# Clock.net
KiCad netlist of a schematic drawn in EAGLE
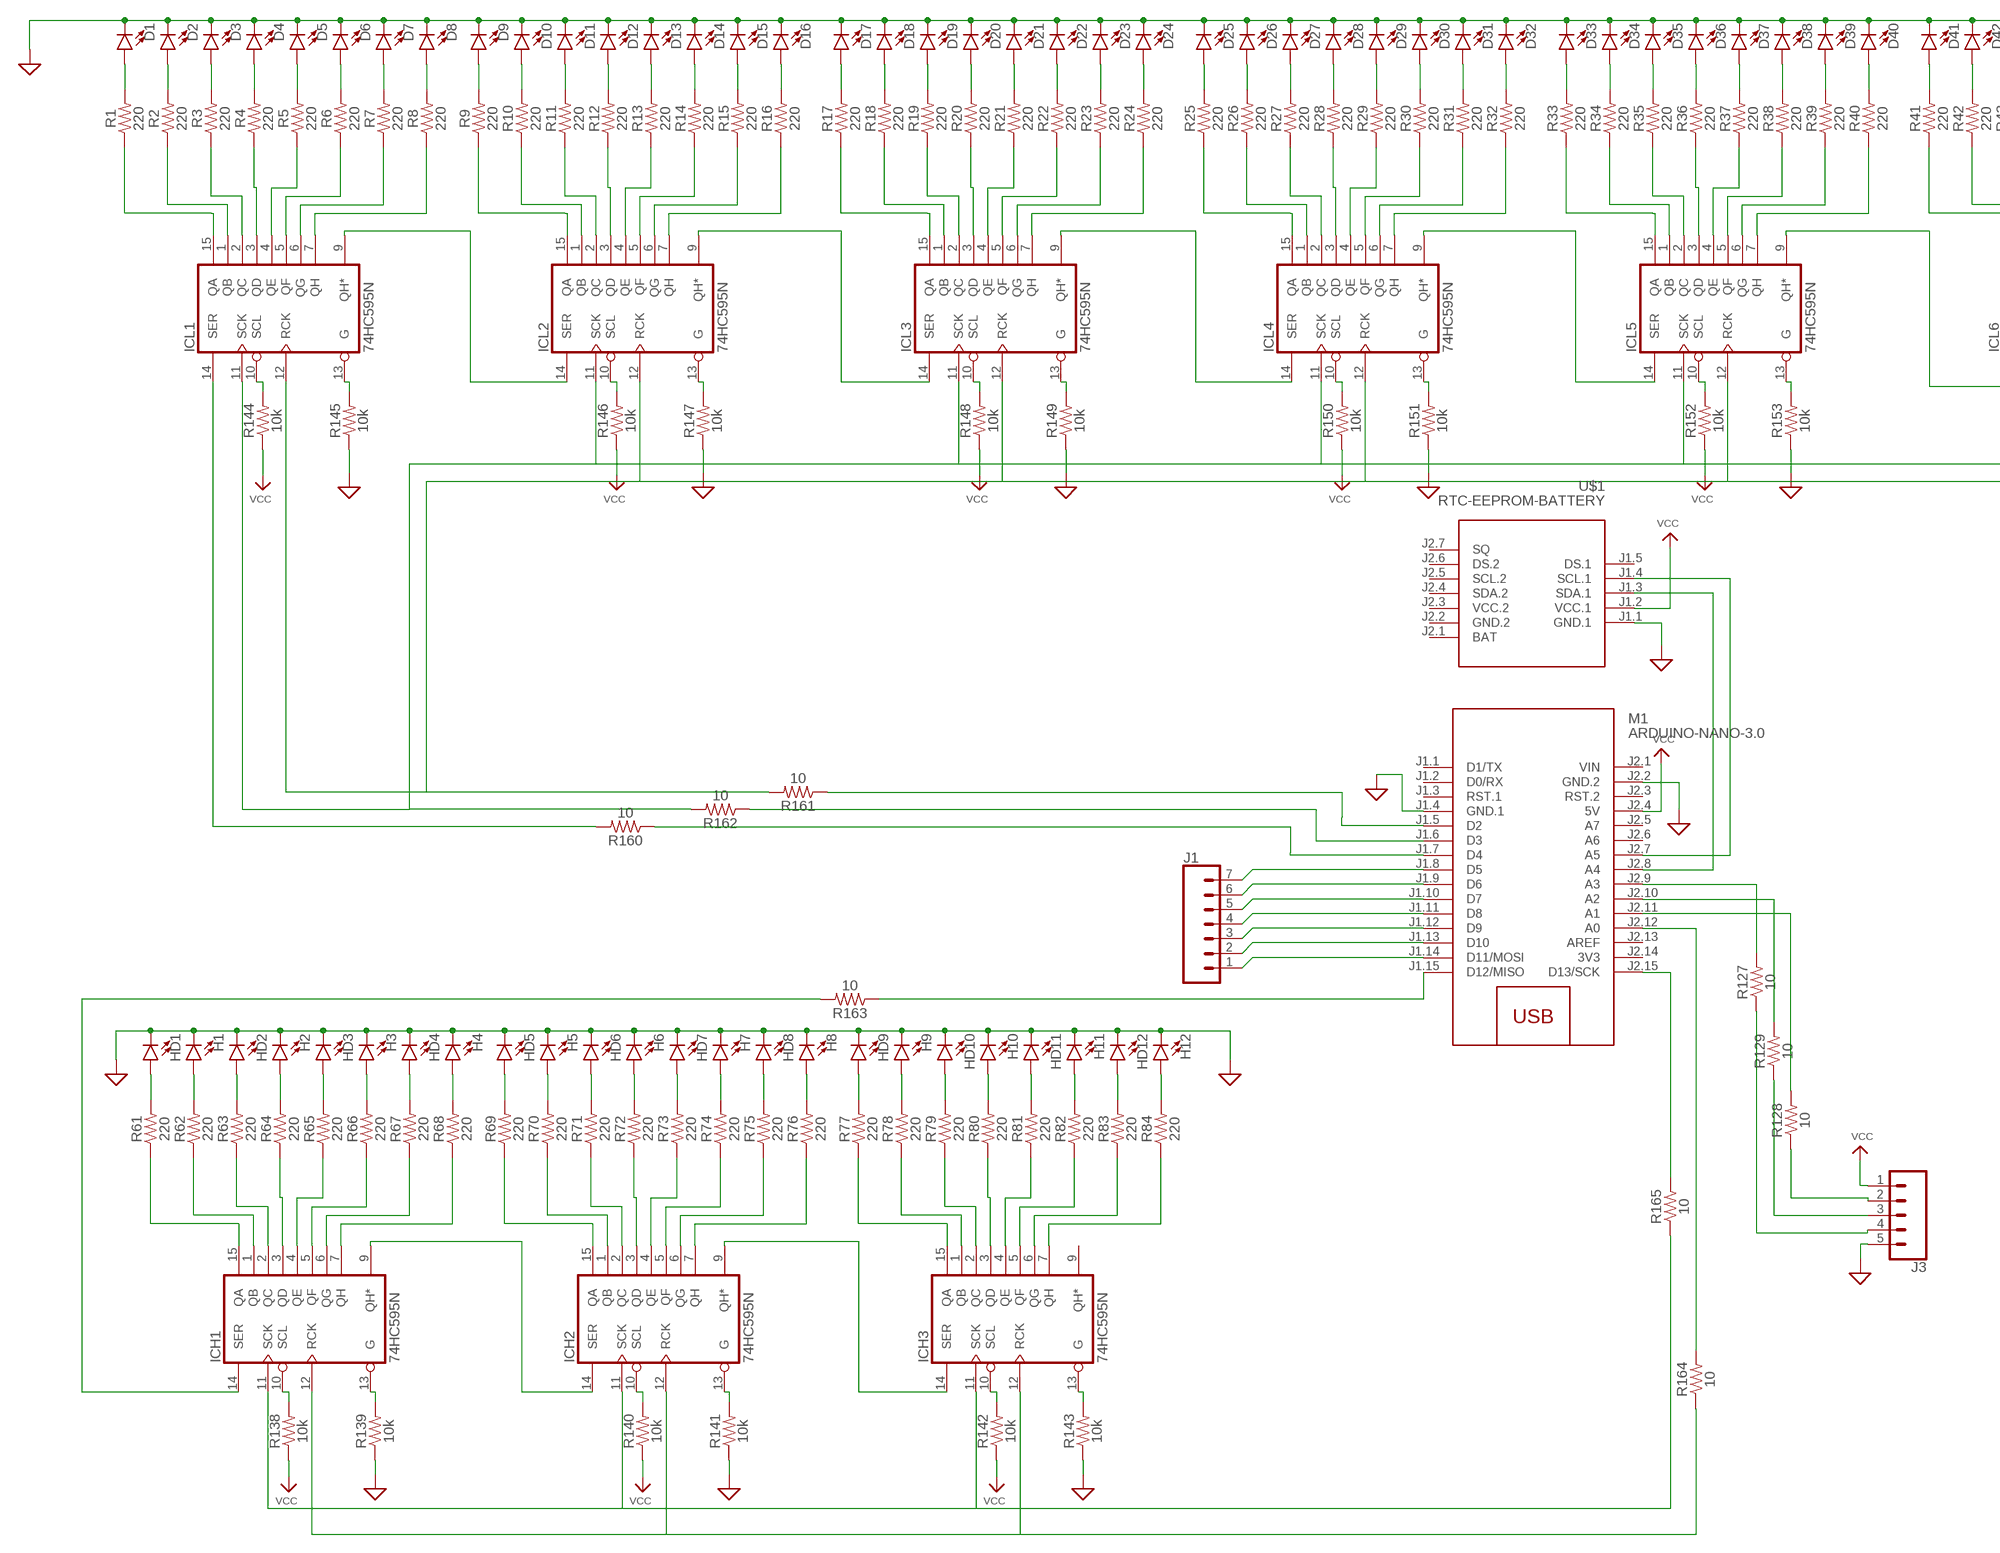
[diagram p0: schematic, sheet 1, part 1 of 2]
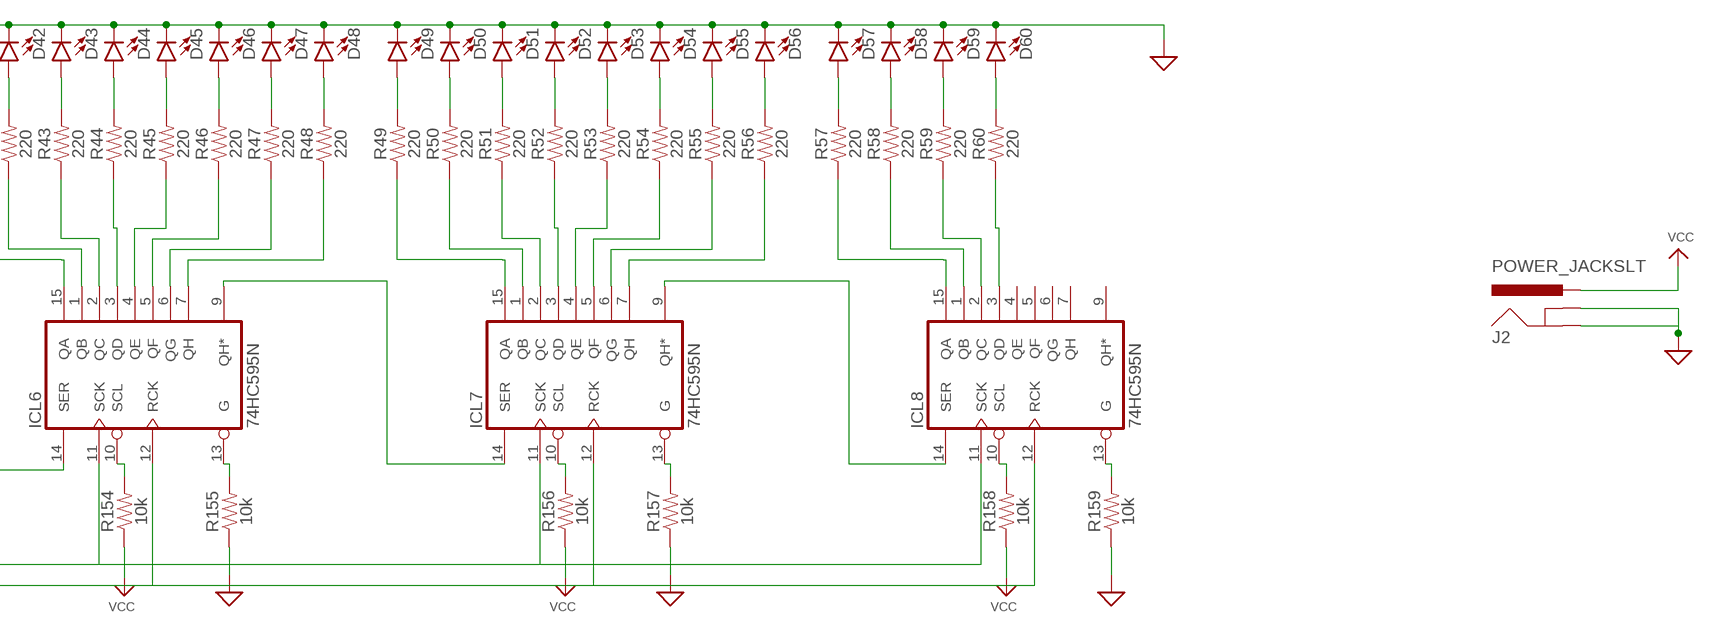
[diagram p1: schematic, sheet 1, part 2 of 2]

(export (version "E")
  (design (tool "Eeschema 10.0.6"))
  (components
    (comp (ref "D1")
      (value "LED5MM")
      (footprint "eagle-import:LED_5MM")
      (libsource (lib "eagle-import") (part "LED5MM"))
    )
    (comp (ref "D2")
      (value "LED5MM")
      (footprint "eagle-import:LED_5MM")
      (libsource (lib "eagle-import") (part "LED5MM"))
    )
    (comp (ref "D3")
      (value "LED5MM")
      (footprint "eagle-import:LED_5MM")
      (libsource (lib "eagle-import") (part "LED5MM"))
    )
    (comp (ref "D4")
      (value "LED5MM")
      (footprint "eagle-import:LED_5MM")
      (libsource (lib "eagle-import") (part "LED5MM"))
    )
    (comp (ref "D5")
      (value "LED5MM")
      (footprint "eagle-import:LED_5MM")
      (libsource (lib "eagle-import") (part "LED5MM"))
    )
    (comp (ref "D6")
      (value "LED5MM")
      (footprint "eagle-import:LED_5MM")
      (libsource (lib "eagle-import") (part "LED5MM"))
    )
    (comp (ref "D7")
      (value "LED5MM")
      (footprint "eagle-import:LED_5MM")
      (libsource (lib "eagle-import") (part "LED5MM"))
    )
    (comp (ref "D8")
      (value "LED5MM")
      (footprint "eagle-import:LED_5MM")
      (libsource (lib "eagle-import") (part "LED5MM"))
    )
    (comp (ref "D9")
      (value "LED5MM")
      (footprint "eagle-import:LED_5MM")
      (libsource (lib "eagle-import") (part "LED5MM"))
    )
    (comp (ref "D10")
      (value "LED5MM")
      (footprint "eagle-import:LED_5MM")
      (libsource (lib "eagle-import") (part "LED5MM"))
    )
    (comp (ref "D11")
      (value "LED5MM")
      (footprint "eagle-import:LED_5MM")
      (libsource (lib "eagle-import") (part "LED5MM"))
    )
    (comp (ref "D12")
      (value "LED5MM")
      (footprint "eagle-import:LED_5MM")
      (libsource (lib "eagle-import") (part "LED5MM"))
    )
    (comp (ref "D13")
      (value "LED5MM")
      (footprint "eagle-import:LED_5MM")
      (libsource (lib "eagle-import") (part "LED5MM"))
    )
    (comp (ref "D14")
      (value "LED5MM")
      (footprint "eagle-import:LED_5MM")
      (libsource (lib "eagle-import") (part "LED5MM"))
    )
    (comp (ref "D15")
      (value "LED5MM")
      (footprint "eagle-import:LED_5MM")
      (libsource (lib "eagle-import") (part "LED5MM"))
    )
    (comp (ref "D16")
      (value "LED5MM")
      (footprint "eagle-import:LED_5MM")
      (libsource (lib "eagle-import") (part "LED5MM"))
    )
    (comp (ref "D17")
      (value "LED5MM")
      (footprint "eagle-import:LED_5MM")
      (libsource (lib "eagle-import") (part "LED5MM"))
    )
    (comp (ref "D18")
      (value "LED5MM")
      (footprint "eagle-import:LED_5MM")
      (libsource (lib "eagle-import") (part "LED5MM"))
    )
    (comp (ref "D19")
      (value "LED5MM")
      (footprint "eagle-import:LED_5MM")
      (libsource (lib "eagle-import") (part "LED5MM"))
    )
    (comp (ref "D20")
      (value "LED5MM")
      (footprint "eagle-import:LED_5MM")
      (libsource (lib "eagle-import") (part "LED5MM"))
    )
    (comp (ref "D21")
      (value "LED5MM")
      (footprint "eagle-import:LED_5MM")
      (libsource (lib "eagle-import") (part "LED5MM"))
    )
    (comp (ref "D22")
      (value "LED5MM")
      (footprint "eagle-import:LED_5MM")
      (libsource (lib "eagle-import") (part "LED5MM"))
    )
    (comp (ref "D23")
      (value "LED5MM")
      (footprint "eagle-import:LED_5MM")
      (libsource (lib "eagle-import") (part "LED5MM"))
    )
    (comp (ref "D24")
      (value "LED5MM")
      (footprint "eagle-import:LED_5MM")
      (libsource (lib "eagle-import") (part "LED5MM"))
    )
    (comp (ref "D25")
      (value "LED5MM")
      (footprint "eagle-import:LED_5MM")
      (libsource (lib "eagle-import") (part "LED5MM"))
    )
    (comp (ref "D26")
      (value "LED5MM")
      (footprint "eagle-import:LED_5MM")
      (libsource (lib "eagle-import") (part "LED5MM"))
    )
    (comp (ref "D27")
      (value "LED5MM")
      (footprint "eagle-import:LED_5MM")
      (libsource (lib "eagle-import") (part "LED5MM"))
    )
    (comp (ref "D28")
      (value "LED5MM")
      (footprint "eagle-import:LED_5MM")
      (libsource (lib "eagle-import") (part "LED5MM"))
    )
    (comp (ref "D29")
      (value "LED5MM")
      (footprint "eagle-import:LED_5MM")
      (libsource (lib "eagle-import") (part "LED5MM"))
    )
    (comp (ref "D30")
      (value "LED5MM")
      (footprint "eagle-import:LED_5MM")
      (libsource (lib "eagle-import") (part "LED5MM"))
    )
    (comp (ref "D31")
      (value "LED5MM")
      (footprint "eagle-import:LED_5MM")
      (libsource (lib "eagle-import") (part "LED5MM"))
    )
    (comp (ref "D32")
      (value "LED5MM")
      (footprint "eagle-import:LED_5MM")
      (libsource (lib "eagle-import") (part "LED5MM"))
    )
    (comp (ref "D33")
      (value "LED5MM")
      (footprint "eagle-import:LED_5MM")
      (libsource (lib "eagle-import") (part "LED5MM"))
    )
    (comp (ref "D34")
      (value "LED5MM")
      (footprint "eagle-import:LED_5MM")
      (libsource (lib "eagle-import") (part "LED5MM"))
    )
    (comp (ref "D35")
      (value "LED5MM")
      (footprint "eagle-import:LED_5MM")
      (libsource (lib "eagle-import") (part "LED5MM"))
    )
    (comp (ref "D36")
      (value "LED5MM")
      (footprint "eagle-import:LED_5MM")
      (libsource (lib "eagle-import") (part "LED5MM"))
    )
    (comp (ref "D37")
      (value "LED5MM")
      (footprint "eagle-import:LED_5MM")
      (libsource (lib "eagle-import") (part "LED5MM"))
    )
    (comp (ref "D38")
      (value "LED5MM")
      (footprint "eagle-import:LED_5MM")
      (libsource (lib "eagle-import") (part "LED5MM"))
    )
    (comp (ref "D39")
      (value "LED5MM")
      (footprint "eagle-import:LED_5MM")
      (libsource (lib "eagle-import") (part "LED5MM"))
    )
    (comp (ref "D40")
      (value "LED5MM")
      (footprint "eagle-import:LED_5MM")
      (libsource (lib "eagle-import") (part "LED5MM"))
    )
    (comp (ref "D41")
      (value "LED5MM")
      (footprint "eagle-import:LED_5MM")
      (libsource (lib "eagle-import") (part "LED5MM"))
    )
    (comp (ref "D42")
      (value "LED5MM")
      (footprint "eagle-import:LED_5MM")
      (libsource (lib "eagle-import") (part "LED5MM"))
    )
    (comp (ref "D43")
      (value "LED5MM")
      (footprint "eagle-import:LED_5MM")
      (libsource (lib "eagle-import") (part "LED5MM"))
    )
    (comp (ref "D44")
      (value "LED5MM")
      (footprint "eagle-import:LED_5MM")
      (libsource (lib "eagle-import") (part "LED5MM"))
    )
    (comp (ref "D45")
      (value "LED5MM")
      (footprint "eagle-import:LED_5MM")
      (libsource (lib "eagle-import") (part "LED5MM"))
    )
    (comp (ref "D46")
      (value "LED5MM")
      (footprint "eagle-import:LED_5MM")
      (libsource (lib "eagle-import") (part "LED5MM"))
    )
    (comp (ref "D47")
      (value "LED5MM")
      (footprint "eagle-import:LED_5MM")
      (libsource (lib "eagle-import") (part "LED5MM"))
    )
    (comp (ref "D48")
      (value "LED5MM")
      (footprint "eagle-import:LED_5MM")
      (libsource (lib "eagle-import") (part "LED5MM"))
    )
    (comp (ref "D49")
      (value "LED5MM")
      (footprint "eagle-import:LED_5MM")
      (libsource (lib "eagle-import") (part "LED5MM"))
    )
    (comp (ref "D50")
      (value "LED5MM")
      (footprint "eagle-import:LED_5MM")
      (libsource (lib "eagle-import") (part "LED5MM"))
    )
    (comp (ref "D51")
      (value "LED5MM")
      (footprint "eagle-import:LED_5MM")
      (libsource (lib "eagle-import") (part "LED5MM"))
    )
    (comp (ref "D52")
      (value "LED5MM")
      (footprint "eagle-import:LED_5MM")
      (libsource (lib "eagle-import") (part "LED5MM"))
    )
    (comp (ref "D53")
      (value "LED5MM")
      (footprint "eagle-import:LED_5MM")
      (libsource (lib "eagle-import") (part "LED5MM"))
    )
    (comp (ref "D54")
      (value "LED5MM")
      (footprint "eagle-import:LED_5MM")
      (libsource (lib "eagle-import") (part "LED5MM"))
    )
    (comp (ref "D55")
      (value "LED5MM")
      (footprint "eagle-import:LED_5MM")
      (libsource (lib "eagle-import") (part "LED5MM"))
    )
    (comp (ref "D56")
      (value "LED5MM")
      (footprint "eagle-import:LED_5MM")
      (libsource (lib "eagle-import") (part "LED5MM"))
    )
    (comp (ref "D57")
      (value "LED5MM")
      (footprint "eagle-import:LED_5MM")
      (libsource (lib "eagle-import") (part "LED5MM"))
    )
    (comp (ref "D58")
      (value "LED5MM")
      (footprint "eagle-import:LED_5MM")
      (libsource (lib "eagle-import") (part "LED5MM"))
    )
    (comp (ref "D59")
      (value "LED5MM")
      (footprint "eagle-import:LED_5MM")
      (libsource (lib "eagle-import") (part "LED5MM"))
    )
    (comp (ref "D60")
      (value "LED5MM")
      (footprint "eagle-import:LED_5MM")
      (libsource (lib "eagle-import") (part "LED5MM"))
    )
    (comp (ref "H1")
      (value "LED5MM")
      (footprint "eagle-import:LED_5MM")
      (libsource (lib "eagle-import") (part "LED5MM"))
    )
    (comp (ref "H2")
      (value "LED5MM")
      (footprint "eagle-import:LED_5MM")
      (libsource (lib "eagle-import") (part "LED5MM"))
    )
    (comp (ref "H3")
      (value "LED5MM")
      (footprint "eagle-import:LED_5MM")
      (libsource (lib "eagle-import") (part "LED5MM"))
    )
    (comp (ref "H4")
      (value "LED5MM")
      (footprint "eagle-import:LED_5MM")
      (libsource (lib "eagle-import") (part "LED5MM"))
    )
    (comp (ref "H5")
      (value "LED5MM")
      (footprint "eagle-import:LED_5MM")
      (libsource (lib "eagle-import") (part "LED5MM"))
    )
    (comp (ref "H6")
      (value "LED5MM")
      (footprint "eagle-import:LED_5MM")
      (libsource (lib "eagle-import") (part "LED5MM"))
    )
    (comp (ref "H7")
      (value "LED5MM")
      (footprint "eagle-import:LED_5MM")
      (libsource (lib "eagle-import") (part "LED5MM"))
    )
    (comp (ref "H8")
      (value "LED5MM")
      (footprint "eagle-import:LED_5MM")
      (libsource (lib "eagle-import") (part "LED5MM"))
    )
    (comp (ref "H9")
      (value "LED5MM")
      (footprint "eagle-import:LED_5MM")
      (libsource (lib "eagle-import") (part "LED5MM"))
    )
    (comp (ref "H10")
      (value "LED5MM")
      (footprint "eagle-import:LED_5MM")
      (libsource (lib "eagle-import") (part "LED5MM"))
    )
    (comp (ref "H11")
      (value "LED5MM")
      (footprint "eagle-import:LED_5MM")
      (libsource (lib "eagle-import") (part "LED5MM"))
    )
    (comp (ref "H12")
      (value "LED5MM")
      (footprint "eagle-import:LED_5MM")
      (libsource (lib "eagle-import") (part "LED5MM"))
    )
    (comp (ref "HD1")
      (value "LED5MM")
      (footprint "eagle-import:LED_5MM")
      (libsource (lib "eagle-import") (part "LED5MM"))
    )
    (comp (ref "HD2")
      (value "LED5MM")
      (footprint "eagle-import:LED_5MM")
      (libsource (lib "eagle-import") (part "LED5MM"))
    )
    (comp (ref "HD3")
      (value "LED5MM")
      (footprint "eagle-import:LED_5MM")
      (libsource (lib "eagle-import") (part "LED5MM"))
    )
    (comp (ref "HD4")
      (value "LED5MM")
      (footprint "eagle-import:LED_5MM")
      (libsource (lib "eagle-import") (part "LED5MM"))
    )
    (comp (ref "HD5")
      (value "LED5MM")
      (footprint "eagle-import:LED_5MM")
      (libsource (lib "eagle-import") (part "LED5MM"))
    )
    (comp (ref "HD6")
      (value "LED5MM")
      (footprint "eagle-import:LED_5MM")
      (libsource (lib "eagle-import") (part "LED5MM"))
    )
    (comp (ref "HD7")
      (value "LED5MM")
      (footprint "eagle-import:LED_5MM")
      (libsource (lib "eagle-import") (part "LED5MM"))
    )
    (comp (ref "HD8")
      (value "LED5MM")
      (footprint "eagle-import:LED_5MM")
      (libsource (lib "eagle-import") (part "LED5MM"))
    )
    (comp (ref "HD9")
      (value "LED5MM")
      (footprint "eagle-import:LED_5MM")
      (libsource (lib "eagle-import") (part "LED5MM"))
    )
    (comp (ref "HD10")
      (value "LED5MM")
      (footprint "eagle-import:LED_5MM")
      (libsource (lib "eagle-import") (part "LED5MM"))
    )
    (comp (ref "HD11")
      (value "LED5MM")
      (footprint "eagle-import:LED_5MM")
      (libsource (lib "eagle-import") (part "LED5MM"))
    )
    (comp (ref "HD12")
      (value "LED5MM")
      (footprint "eagle-import:LED_5MM")
      (libsource (lib "eagle-import") (part "LED5MM"))
    )
    (comp (ref "ICH1")
      (value "74HC595N")
      (footprint "eagle-import:DIL16")
      (libsource (lib "eagle-import") (part "74595NHC"))
    )
    (comp (ref "ICH2")
      (value "74HC595N")
      (footprint "eagle-import:DIL16")
      (libsource (lib "eagle-import") (part "74595NHC"))
    )
    (comp (ref "ICH3")
      (value "74HC595N")
      (footprint "eagle-import:DIL16")
      (libsource (lib "eagle-import") (part "74595NHC"))
    )
    (comp (ref "ICL1")
      (value "74HC595N")
      (footprint "eagle-import:DIL16")
      (libsource (lib "eagle-import") (part "74595NHC"))
    )
    (comp (ref "ICL2")
      (value "74HC595N")
      (footprint "eagle-import:DIL16")
      (libsource (lib "eagle-import") (part "74595NHC"))
    )
    (comp (ref "ICL3")
      (value "74HC595N")
      (footprint "eagle-import:DIL16")
      (libsource (lib "eagle-import") (part "74595NHC"))
    )
    (comp (ref "ICL4")
      (value "74HC595N")
      (footprint "eagle-import:DIL16")
      (libsource (lib "eagle-import") (part "74595NHC"))
    )
    (comp (ref "ICL5")
      (value "74HC595N")
      (footprint "eagle-import:DIL16")
      (libsource (lib "eagle-import") (part "74595NHC"))
    )
    (comp (ref "ICL6")
      (value "74HC595N")
      (footprint "eagle-import:DIL16")
      (libsource (lib "eagle-import") (part "74595NHC"))
    )
    (comp (ref "ICL7")
      (value "74HC595N")
      (footprint "eagle-import:DIL16")
      (libsource (lib "eagle-import") (part "74595NHC"))
    )
    (comp (ref "ICL8")
      (value "74HC595N")
      (footprint "eagle-import:DIL16")
      (libsource (lib "eagle-import") (part "74595NHC"))
    )
    (comp (ref "J1")
      (value "CONN_07LOCK_LONGPADS")
      (footprint "eagle-import:1X07_LOCK_LONGPADS")
      (libsource (lib "eagle-import") (part "CONN_07LOCK_LONGPADS"))
    )
    (comp (ref "J2")
      (value "POWER_JACKSLT")
      (footprint "eagle-import:POWER_JACK_SLOT")
      (libsource (lib "eagle-import") (part "POWER_JACKSLT"))
    )
    (comp (ref "J3")
      (value "CONN_05LOCK_LONGPADS")
      (footprint "eagle-import:1X05_LOCK_LONGPADS")
      (libsource (lib "eagle-import") (part "CONN_05LOCK_LONGPADS"))
    )
    (comp (ref "M1")
      (value "ARDUINO-NANO-3.0")
      (footprint "eagle-import:ARDUINO-NANO-3.0")
      (libsource (lib "eagle-import") (part "ARDUINO-NANO-3.0"))
    )
    (comp (ref "R1")
      (value "220")
      (footprint "eagle-import:AXIAL-0.3")
      (libsource (lib "eagle-import") (part "1KOHM-HORIZ-1/4W-1%"))
    )
    (comp (ref "R2")
      (value "220")
      (footprint "eagle-import:AXIAL-0.3")
      (libsource (lib "eagle-import") (part "1KOHM-HORIZ-1/4W-1%"))
    )
    (comp (ref "R3")
      (value "220")
      (footprint "eagle-import:AXIAL-0.3")
      (libsource (lib "eagle-import") (part "1KOHM-HORIZ-1/4W-1%"))
    )
    (comp (ref "R4")
      (value "220")
      (footprint "eagle-import:AXIAL-0.3")
      (libsource (lib "eagle-import") (part "1KOHM-HORIZ-1/4W-1%"))
    )
    (comp (ref "R5")
      (value "220")
      (footprint "eagle-import:AXIAL-0.3")
      (libsource (lib "eagle-import") (part "1KOHM-HORIZ-1/4W-1%"))
    )
    (comp (ref "R6")
      (value "220")
      (footprint "eagle-import:AXIAL-0.3")
      (libsource (lib "eagle-import") (part "1KOHM-HORIZ-1/4W-1%"))
    )
    (comp (ref "R7")
      (value "220")
      (footprint "eagle-import:AXIAL-0.3")
      (libsource (lib "eagle-import") (part "1KOHM-HORIZ-1/4W-1%"))
    )
    (comp (ref "R8")
      (value "220")
      (footprint "eagle-import:AXIAL-0.3")
      (libsource (lib "eagle-import") (part "1KOHM-HORIZ-1/4W-1%"))
    )
    (comp (ref "R9")
      (value "220")
      (footprint "eagle-import:AXIAL-0.3")
      (libsource (lib "eagle-import") (part "1KOHM-HORIZ-1/4W-1%"))
    )
    (comp (ref "R10")
      (value "220")
      (footprint "eagle-import:AXIAL-0.3")
      (libsource (lib "eagle-import") (part "1KOHM-HORIZ-1/4W-1%"))
    )
    (comp (ref "R11")
      (value "220")
      (footprint "eagle-import:AXIAL-0.3")
      (libsource (lib "eagle-import") (part "1KOHM-HORIZ-1/4W-1%"))
    )
    (comp (ref "R12")
      (value "220")
      (footprint "eagle-import:AXIAL-0.3")
      (libsource (lib "eagle-import") (part "1KOHM-HORIZ-1/4W-1%"))
    )
    (comp (ref "R13")
      (value "220")
      (footprint "eagle-import:AXIAL-0.3")
      (libsource (lib "eagle-import") (part "1KOHM-HORIZ-1/4W-1%"))
    )
    (comp (ref "R14")
      (value "220")
      (footprint "eagle-import:AXIAL-0.3")
      (libsource (lib "eagle-import") (part "1KOHM-HORIZ-1/4W-1%"))
    )
    (comp (ref "R15")
      (value "220")
      (footprint "eagle-import:AXIAL-0.3")
      (libsource (lib "eagle-import") (part "1KOHM-HORIZ-1/4W-1%"))
    )
    (comp (ref "R16")
      (value "220")
      (footprint "eagle-import:AXIAL-0.3")
      (libsource (lib "eagle-import") (part "1KOHM-HORIZ-1/4W-1%"))
    )
    (comp (ref "R17")
      (value "220")
      (footprint "eagle-import:AXIAL-0.3")
      (libsource (lib "eagle-import") (part "1KOHM-HORIZ-1/4W-1%"))
    )
    (comp (ref "R18")
      (value "220")
      (footprint "eagle-import:AXIAL-0.3")
      (libsource (lib "eagle-import") (part "1KOHM-HORIZ-1/4W-1%"))
    )
    (comp (ref "R19")
      (value "220")
      (footprint "eagle-import:AXIAL-0.3")
      (libsource (lib "eagle-import") (part "1KOHM-HORIZ-1/4W-1%"))
    )
    (comp (ref "R20")
      (value "220")
      (footprint "eagle-import:AXIAL-0.3")
      (libsource (lib "eagle-import") (part "1KOHM-HORIZ-1/4W-1%"))
    )
    (comp (ref "R21")
      (value "220")
      (footprint "eagle-import:AXIAL-0.3")
      (libsource (lib "eagle-import") (part "1KOHM-HORIZ-1/4W-1%"))
    )
    (comp (ref "R22")
      (value "220")
      (footprint "eagle-import:AXIAL-0.3")
      (libsource (lib "eagle-import") (part "1KOHM-HORIZ-1/4W-1%"))
    )
    (comp (ref "R23")
      (value "220")
      (footprint "eagle-import:AXIAL-0.3")
      (libsource (lib "eagle-import") (part "1KOHM-HORIZ-1/4W-1%"))
    )
    (comp (ref "R24")
      (value "220")
      (footprint "eagle-import:AXIAL-0.3")
      (libsource (lib "eagle-import") (part "1KOHM-HORIZ-1/4W-1%"))
    )
    (comp (ref "R25")
      (value "220")
      (footprint "eagle-import:AXIAL-0.3")
      (libsource (lib "eagle-import") (part "1KOHM-HORIZ-1/4W-1%"))
    )
    (comp (ref "R26")
      (value "220")
      (footprint "eagle-import:AXIAL-0.3")
      (libsource (lib "eagle-import") (part "1KOHM-HORIZ-1/4W-1%"))
    )
    (comp (ref "R27")
      (value "220")
      (footprint "eagle-import:AXIAL-0.3")
      (libsource (lib "eagle-import") (part "1KOHM-HORIZ-1/4W-1%"))
    )
    (comp (ref "R28")
      (value "220")
      (footprint "eagle-import:AXIAL-0.3")
      (libsource (lib "eagle-import") (part "1KOHM-HORIZ-1/4W-1%"))
    )
    (comp (ref "R29")
      (value "220")
      (footprint "eagle-import:AXIAL-0.3")
      (libsource (lib "eagle-import") (part "1KOHM-HORIZ-1/4W-1%"))
    )
    (comp (ref "R30")
      (value "220")
      (footprint "eagle-import:AXIAL-0.3")
      (libsource (lib "eagle-import") (part "1KOHM-HORIZ-1/4W-1%"))
    )
    (comp (ref "R31")
      (value "220")
      (footprint "eagle-import:AXIAL-0.3")
      (libsource (lib "eagle-import") (part "1KOHM-HORIZ-1/4W-1%"))
    )
    (comp (ref "R32")
      (value "220")
      (footprint "eagle-import:AXIAL-0.3")
      (libsource (lib "eagle-import") (part "1KOHM-HORIZ-1/4W-1%"))
    )
    (comp (ref "R33")
      (value "220")
      (footprint "eagle-import:AXIAL-0.3")
      (libsource (lib "eagle-import") (part "1KOHM-HORIZ-1/4W-1%"))
    )
    (comp (ref "R34")
      (value "220")
      (footprint "eagle-import:AXIAL-0.3")
      (libsource (lib "eagle-import") (part "1KOHM-HORIZ-1/4W-1%"))
    )
    (comp (ref "R35")
      (value "220")
      (footprint "eagle-import:AXIAL-0.3")
      (libsource (lib "eagle-import") (part "1KOHM-HORIZ-1/4W-1%"))
    )
    (comp (ref "R36")
      (value "220")
      (footprint "eagle-import:AXIAL-0.3")
      (libsource (lib "eagle-import") (part "1KOHM-HORIZ-1/4W-1%"))
    )
    (comp (ref "R37")
      (value "220")
      (footprint "eagle-import:AXIAL-0.3")
      (libsource (lib "eagle-import") (part "1KOHM-HORIZ-1/4W-1%"))
    )
    (comp (ref "R38")
      (value "220")
      (footprint "eagle-import:AXIAL-0.3")
      (libsource (lib "eagle-import") (part "1KOHM-HORIZ-1/4W-1%"))
    )
    (comp (ref "R39")
      (value "220")
      (footprint "eagle-import:AXIAL-0.3")
      (libsource (lib "eagle-import") (part "1KOHM-HORIZ-1/4W-1%"))
    )
    (comp (ref "R40")
      (value "220")
      (footprint "eagle-import:AXIAL-0.3")
      (libsource (lib "eagle-import") (part "1KOHM-HORIZ-1/4W-1%"))
    )
    (comp (ref "R41")
      (value "220")
      (footprint "eagle-import:AXIAL-0.3")
      (libsource (lib "eagle-import") (part "1KOHM-HORIZ-1/4W-1%"))
    )
    (comp (ref "R42")
      (value "220")
      (footprint "eagle-import:AXIAL-0.3")
      (libsource (lib "eagle-import") (part "1KOHM-HORIZ-1/4W-1%"))
    )
    (comp (ref "R43")
      (value "220")
      (footprint "eagle-import:AXIAL-0.3")
      (libsource (lib "eagle-import") (part "1KOHM-HORIZ-1/4W-1%"))
    )
    (comp (ref "R44")
      (value "220")
      (footprint "eagle-import:AXIAL-0.3")
      (libsource (lib "eagle-import") (part "1KOHM-HORIZ-1/4W-1%"))
    )
    (comp (ref "R45")
      (value "220")
      (footprint "eagle-import:AXIAL-0.3")
      (libsource (lib "eagle-import") (part "1KOHM-HORIZ-1/4W-1%"))
    )
    (comp (ref "R46")
      (value "220")
      (footprint "eagle-import:AXIAL-0.3")
      (libsource (lib "eagle-import") (part "1KOHM-HORIZ-1/4W-1%"))
    )
    (comp (ref "R47")
      (value "220")
      (footprint "eagle-import:AXIAL-0.3")
      (libsource (lib "eagle-import") (part "1KOHM-HORIZ-1/4W-1%"))
    )
    (comp (ref "R48")
      (value "220")
      (footprint "eagle-import:AXIAL-0.3")
      (libsource (lib "eagle-import") (part "1KOHM-HORIZ-1/4W-1%"))
    )
    (comp (ref "R49")
      (value "220")
      (footprint "eagle-import:AXIAL-0.3")
      (libsource (lib "eagle-import") (part "1KOHM-HORIZ-1/4W-1%"))
    )
    (comp (ref "R50")
      (value "220")
      (footprint "eagle-import:AXIAL-0.3")
      (libsource (lib "eagle-import") (part "1KOHM-HORIZ-1/4W-1%"))
    )
    (comp (ref "R51")
      (value "220")
      (footprint "eagle-import:AXIAL-0.3")
      (libsource (lib "eagle-import") (part "1KOHM-HORIZ-1/4W-1%"))
    )
    (comp (ref "R52")
      (value "220")
      (footprint "eagle-import:AXIAL-0.3")
      (libsource (lib "eagle-import") (part "1KOHM-HORIZ-1/4W-1%"))
    )
    (comp (ref "R53")
      (value "220")
      (footprint "eagle-import:AXIAL-0.3")
      (libsource (lib "eagle-import") (part "1KOHM-HORIZ-1/4W-1%"))
    )
    (comp (ref "R54")
      (value "220")
      (footprint "eagle-import:AXIAL-0.3")
      (libsource (lib "eagle-import") (part "1KOHM-HORIZ-1/4W-1%"))
    )
    (comp (ref "R55")
      (value "220")
      (footprint "eagle-import:AXIAL-0.3")
      (libsource (lib "eagle-import") (part "1KOHM-HORIZ-1/4W-1%"))
    )
    (comp (ref "R56")
      (value "220")
      (footprint "eagle-import:AXIAL-0.3")
      (libsource (lib "eagle-import") (part "1KOHM-HORIZ-1/4W-1%"))
    )
    (comp (ref "R57")
      (value "220")
      (footprint "eagle-import:AXIAL-0.3")
      (libsource (lib "eagle-import") (part "1KOHM-HORIZ-1/4W-1%"))
    )
    (comp (ref "R58")
      (value "220")
      (footprint "eagle-import:AXIAL-0.3")
      (libsource (lib "eagle-import") (part "1KOHM-HORIZ-1/4W-1%"))
    )
    (comp (ref "R59")
      (value "220")
      (footprint "eagle-import:AXIAL-0.3")
      (libsource (lib "eagle-import") (part "1KOHM-HORIZ-1/4W-1%"))
    )
    (comp (ref "R60")
      (value "220")
      (footprint "eagle-import:AXIAL-0.3")
      (libsource (lib "eagle-import") (part "1KOHM-HORIZ-1/4W-1%"))
    )
    (comp (ref "R61")
      (value "220")
      (footprint "eagle-import:AXIAL-0.3")
      (libsource (lib "eagle-import") (part "1KOHM-HORIZ-1/4W-1%"))
    )
    (comp (ref "R62")
      (value "220")
      (footprint "eagle-import:AXIAL-0.3")
      (libsource (lib "eagle-import") (part "1KOHM-HORIZ-1/4W-1%"))
    )
    (comp (ref "R63")
      (value "220")
      (footprint "eagle-import:AXIAL-0.3")
      (libsource (lib "eagle-import") (part "1KOHM-HORIZ-1/4W-1%"))
    )
    (comp (ref "R64")
      (value "220")
      (footprint "eagle-import:AXIAL-0.3")
      (libsource (lib "eagle-import") (part "1KOHM-HORIZ-1/4W-1%"))
    )
    (comp (ref "R65")
      (value "220")
      (footprint "eagle-import:AXIAL-0.3")
      (libsource (lib "eagle-import") (part "1KOHM-HORIZ-1/4W-1%"))
    )
    (comp (ref "R66")
      (value "220")
      (footprint "eagle-import:AXIAL-0.3")
      (libsource (lib "eagle-import") (part "1KOHM-HORIZ-1/4W-1%"))
    )
    (comp (ref "R67")
      (value "220")
      (footprint "eagle-import:AXIAL-0.3")
      (libsource (lib "eagle-import") (part "1KOHM-HORIZ-1/4W-1%"))
    )
    (comp (ref "R68")
      (value "220")
      (footprint "eagle-import:AXIAL-0.3")
      (libsource (lib "eagle-import") (part "1KOHM-HORIZ-1/4W-1%"))
    )
    (comp (ref "R69")
      (value "220")
      (footprint "eagle-import:AXIAL-0.3")
      (libsource (lib "eagle-import") (part "1KOHM-HORIZ-1/4W-1%"))
    )
    (comp (ref "R70")
      (value "220")
      (footprint "eagle-import:AXIAL-0.3")
      (libsource (lib "eagle-import") (part "1KOHM-HORIZ-1/4W-1%"))
    )
    (comp (ref "R71")
      (value "220")
      (footprint "eagle-import:AXIAL-0.3")
      (libsource (lib "eagle-import") (part "1KOHM-HORIZ-1/4W-1%"))
    )
    (comp (ref "R72")
      (value "220")
      (footprint "eagle-import:AXIAL-0.3")
      (libsource (lib "eagle-import") (part "1KOHM-HORIZ-1/4W-1%"))
    )
    (comp (ref "R73")
      (value "220")
      (footprint "eagle-import:AXIAL-0.3")
      (libsource (lib "eagle-import") (part "1KOHM-HORIZ-1/4W-1%"))
    )
    (comp (ref "R74")
      (value "220")
      (footprint "eagle-import:AXIAL-0.3")
      (libsource (lib "eagle-import") (part "1KOHM-HORIZ-1/4W-1%"))
    )
    (comp (ref "R75")
      (value "220")
      (footprint "eagle-import:AXIAL-0.3")
      (libsource (lib "eagle-import") (part "1KOHM-HORIZ-1/4W-1%"))
    )
    (comp (ref "R76")
      (value "220")
      (footprint "eagle-import:AXIAL-0.3")
      (libsource (lib "eagle-import") (part "1KOHM-HORIZ-1/4W-1%"))
    )
    (comp (ref "R77")
      (value "220")
      (footprint "eagle-import:AXIAL-0.3")
      (libsource (lib "eagle-import") (part "1KOHM-HORIZ-1/4W-1%"))
    )
    (comp (ref "R78")
      (value "220")
      (footprint "eagle-import:AXIAL-0.3")
      (libsource (lib "eagle-import") (part "1KOHM-HORIZ-1/4W-1%"))
    )
    (comp (ref "R79")
      (value "220")
      (footprint "eagle-import:AXIAL-0.3")
      (libsource (lib "eagle-import") (part "1KOHM-HORIZ-1/4W-1%"))
    )
    (comp (ref "R80")
      (value "220")
      (footprint "eagle-import:AXIAL-0.3")
      (libsource (lib "eagle-import") (part "1KOHM-HORIZ-1/4W-1%"))
    )
    (comp (ref "R81")
      (value "220")
      (footprint "eagle-import:AXIAL-0.3")
      (libsource (lib "eagle-import") (part "1KOHM-HORIZ-1/4W-1%"))
    )
    (comp (ref "R82")
      (value "220")
      (footprint "eagle-import:AXIAL-0.3")
      (libsource (lib "eagle-import") (part "1KOHM-HORIZ-1/4W-1%"))
    )
    (comp (ref "R83")
      (value "220")
      (footprint "eagle-import:AXIAL-0.3")
      (libsource (lib "eagle-import") (part "1KOHM-HORIZ-1/4W-1%"))
    )
    (comp (ref "R84")
      (value "220")
      (footprint "eagle-import:AXIAL-0.3")
      (libsource (lib "eagle-import") (part "1KOHM-HORIZ-1/4W-1%"))
    )
    (comp (ref "R127")
      (value "10")
      (footprint "eagle-import:AXIAL-0.3")
      (libsource (lib "eagle-import") (part "10OHM-HORIZ-1/4W-1%"))
    )
    (comp (ref "R128")
      (value "10")
      (footprint "eagle-import:AXIAL-0.3")
      (libsource (lib "eagle-import") (part "10OHM-HORIZ-1/4W-1%"))
    )
    (comp (ref "R129")
      (value "10")
      (footprint "eagle-import:AXIAL-0.3")
      (libsource (lib "eagle-import") (part "10OHM-HORIZ-1/4W-1%"))
    )
    (comp (ref "R138")
      (value "10k")
      (footprint "eagle-import:AXIAL-0.3")
      (libsource (lib "eagle-import") (part "10KOHM-HORIZ-1/6W-5%"))
    )
    (comp (ref "R139")
      (value "10k")
      (footprint "eagle-import:AXIAL-0.3")
      (libsource (lib "eagle-import") (part "10KOHM-HORIZ-1/6W-5%"))
    )
    (comp (ref "R140")
      (value "10k")
      (footprint "eagle-import:AXIAL-0.3")
      (libsource (lib "eagle-import") (part "10KOHM-HORIZ-1/6W-5%"))
    )
    (comp (ref "R141")
      (value "10k")
      (footprint "eagle-import:AXIAL-0.3")
      (libsource (lib "eagle-import") (part "10KOHM-HORIZ-1/6W-5%"))
    )
    (comp (ref "R142")
      (value "10k")
      (footprint "eagle-import:AXIAL-0.3")
      (libsource (lib "eagle-import") (part "10KOHM-HORIZ-1/6W-5%"))
    )
    (comp (ref "R143")
      (value "10k")
      (footprint "eagle-import:AXIAL-0.3")
      (libsource (lib "eagle-import") (part "10KOHM-HORIZ-1/6W-5%"))
    )
    (comp (ref "R144")
      (value "10k")
      (footprint "eagle-import:AXIAL-0.3")
      (libsource (lib "eagle-import") (part "10KOHM-HORIZ-1/6W-5%"))
    )
    (comp (ref "R145")
      (value "10k")
      (footprint "eagle-import:AXIAL-0.3")
      (libsource (lib "eagle-import") (part "10KOHM-HORIZ-1/6W-5%"))
    )
    (comp (ref "R146")
      (value "10k")
      (footprint "eagle-import:AXIAL-0.3")
      (libsource (lib "eagle-import") (part "10KOHM-HORIZ-1/6W-5%"))
    )
    (comp (ref "R147")
      (value "10k")
      (footprint "eagle-import:AXIAL-0.3")
      (libsource (lib "eagle-import") (part "10KOHM-HORIZ-1/6W-5%"))
    )
    (comp (ref "R148")
      (value "10k")
      (footprint "eagle-import:AXIAL-0.3")
      (libsource (lib "eagle-import") (part "10KOHM-HORIZ-1/6W-5%"))
    )
    (comp (ref "R149")
      (value "10k")
      (footprint "eagle-import:AXIAL-0.3")
      (libsource (lib "eagle-import") (part "10KOHM-HORIZ-1/6W-5%"))
    )
    (comp (ref "R150")
      (value "10k")
      (footprint "eagle-import:AXIAL-0.3")
      (libsource (lib "eagle-import") (part "10KOHM-HORIZ-1/6W-5%"))
    )
    (comp (ref "R151")
      (value "10k")
      (footprint "eagle-import:AXIAL-0.3")
      (libsource (lib "eagle-import") (part "10KOHM-HORIZ-1/6W-5%"))
    )
    (comp (ref "R152")
      (value "10k")
      (footprint "eagle-import:AXIAL-0.3")
      (libsource (lib "eagle-import") (part "10KOHM-HORIZ-1/6W-5%"))
    )
    (comp (ref "R153")
      (value "10k")
      (footprint "eagle-import:AXIAL-0.3")
      (libsource (lib "eagle-import") (part "10KOHM-HORIZ-1/6W-5%"))
    )
    (comp (ref "R154")
      (value "10k")
      (footprint "eagle-import:AXIAL-0.3")
      (libsource (lib "eagle-import") (part "10KOHM-HORIZ-1/6W-5%"))
    )
    (comp (ref "R155")
      (value "10k")
      (footprint "eagle-import:AXIAL-0.3")
      (libsource (lib "eagle-import") (part "10KOHM-HORIZ-1/6W-5%"))
    )
    (comp (ref "R156")
      (value "10k")
      (footprint "eagle-import:AXIAL-0.3")
      (libsource (lib "eagle-import") (part "10KOHM-HORIZ-1/6W-5%"))
    )
    (comp (ref "R157")
      (value "10k")
      (footprint "eagle-import:AXIAL-0.3")
      (libsource (lib "eagle-import") (part "10KOHM-HORIZ-1/6W-5%"))
    )
    (comp (ref "R158")
      (value "10k")
      (footprint "eagle-import:AXIAL-0.3")
      (libsource (lib "eagle-import") (part "10KOHM-HORIZ-1/6W-5%"))
    )
    (comp (ref "R159")
      (value "10k")
      (footprint "eagle-import:AXIAL-0.3")
      (libsource (lib "eagle-import") (part "10KOHM-HORIZ-1/6W-5%"))
    )
    (comp (ref "R160")
      (value "10")
      (footprint "eagle-import:AXIAL-0.3")
      (libsource (lib "eagle-import") (part "10OHM-HORIZ-1/4W-1%"))
    )
    (comp (ref "R161")
      (value "10")
      (footprint "eagle-import:AXIAL-0.3")
      (libsource (lib "eagle-import") (part "10OHM-HORIZ-1/4W-1%"))
    )
    (comp (ref "R162")
      (value "10")
      (footprint "eagle-import:AXIAL-0.3")
      (libsource (lib "eagle-import") (part "10OHM-HORIZ-1/4W-1%"))
    )
    (comp (ref "R163")
      (value "10")
      (footprint "eagle-import:AXIAL-0.3")
      (libsource (lib "eagle-import") (part "10OHM-HORIZ-1/4W-1%"))
    )
    (comp (ref "R164")
      (value "10")
      (footprint "eagle-import:AXIAL-0.3")
      (libsource (lib "eagle-import") (part "10OHM-HORIZ-1/4W-1%"))
    )
    (comp (ref "R165")
      (value "10")
      (footprint "eagle-import:AXIAL-0.3")
      (libsource (lib "eagle-import") (part "10OHM-HORIZ-1/4W-1%"))
    )
    (comp (ref "U$1")
      (value "RTC-EEPROM-BATTERY")
      (footprint "eagle-import:RTC-EEPROM-BATTERY")
      (libsource (lib "eagle-import") (part "RTC-EEPROM-BATTERY"))
    )
  )
  (nets
    (net (code "1") (name "/3V3") (class "Default")
      (node (ref "M1") (pin "J2.14") (pinfunction "3V3_J2.14") (pintype "power_in"))
    )
    (net (code "2") (name "/GND.2") (class "Default")
      (node (ref "U$1") (pin "J2.2") (pinfunction "GND.2_J2.2") (pintype "power_in"))
    )
    (net (code "3") (name "/VCC.2") (class "Default")
      (node (ref "U$1") (pin "J2.3") (pinfunction "VCC.2_J2.3") (pintype "power_in"))
    )
    (net (code "4") (name "/VIN") (class "Default")
      (node (ref "M1") (pin "J2.1") (pinfunction "VIN_J2.1") (pintype "power_in"))
    )
    (net (code "5") (name "Net-(ICH1A-G)") (class "Default")
      (node (ref "ICH1") (pin "13") (pinfunction "G_13") (pintype "input"))
      (node (ref "R139") (pin "P$2") (pinfunction "2_P$2") (pintype "passive"))
    )
    (net (code "6") (name "Net-(ICH1A-QA)") (class "Default")
      (node (ref "ICH1") (pin "15") (pinfunction "QA_15") (pintype "tri_state"))
      (node (ref "R61") (pin "P$1") (pinfunction "1_P$1") (pintype "passive"))
    )
    (net (code "7") (name "Net-(ICH1A-QB)") (class "Default")
      (node (ref "ICH1") (pin "1") (pinfunction "QB_1") (pintype "tri_state"))
      (node (ref "R62") (pin "P$1") (pinfunction "1_P$1") (pintype "passive"))
    )
    (net (code "8") (name "Net-(ICH1A-QC)") (class "Default")
      (node (ref "ICH1") (pin "2") (pinfunction "QC_2") (pintype "tri_state"))
      (node (ref "R63") (pin "P$1") (pinfunction "1_P$1") (pintype "passive"))
    )
    (net (code "9") (name "Net-(ICH1A-QD)") (class "Default")
      (node (ref "ICH1") (pin "3") (pinfunction "QD_3") (pintype "tri_state"))
      (node (ref "R64") (pin "P$1") (pinfunction "1_P$1") (pintype "passive"))
    )
    (net (code "10") (name "Net-(ICH1A-QE)") (class "Default")
      (node (ref "ICH1") (pin "4") (pinfunction "QE_4") (pintype "tri_state"))
      (node (ref "R65") (pin "P$1") (pinfunction "1_P$1") (pintype "passive"))
    )
    (net (code "11") (name "Net-(ICH1A-QF)") (class "Default")
      (node (ref "ICH1") (pin "5") (pinfunction "QF_5") (pintype "tri_state"))
      (node (ref "R66") (pin "P$1") (pinfunction "1_P$1") (pintype "passive"))
    )
    (net (code "12") (name "Net-(ICH1A-QG)") (class "Default")
      (node (ref "ICH1") (pin "6") (pinfunction "QG_6") (pintype "tri_state"))
      (node (ref "R67") (pin "P$1") (pinfunction "1_P$1") (pintype "passive"))
    )
    (net (code "13") (name "Net-(ICH1A-QH)") (class "Default")
      (node (ref "ICH1") (pin "7") (pinfunction "QH_7") (pintype "tri_state"))
      (node (ref "R68") (pin "P$1") (pinfunction "1_P$1") (pintype "passive"))
    )
    (net (code "14") (name "Net-(ICH1A-QH*)") (class "Default")
      (node (ref "ICH1") (pin "9") (pinfunction "QH*_9") (pintype "tri_state"))
      (node (ref "ICH2") (pin "14") (pinfunction "SER_14") (pintype "input"))
    )
    (net (code "15") (name "Net-(ICH1A-RCK)") (class "Default")
      (node (ref "ICH1") (pin "12") (pinfunction "RCK_12") (pintype "input"))
      (node (ref "ICH2") (pin "12") (pinfunction "RCK_12") (pintype "input"))
      (node (ref "ICH3") (pin "12") (pinfunction "RCK_12") (pintype "input"))
      (node (ref "R164") (pin "P$1") (pinfunction "1_P$1") (pintype "passive"))
    )
    (net (code "16") (name "Net-(ICH1A-SCK)") (class "Default")
      (node (ref "ICH1") (pin "11") (pinfunction "SCK_11") (pintype "input"))
      (node (ref "ICH2") (pin "11") (pinfunction "SCK_11") (pintype "input"))
      (node (ref "ICH3") (pin "11") (pinfunction "SCK_11") (pintype "input"))
      (node (ref "R165") (pin "P$1") (pinfunction "1_P$1") (pintype "passive"))
    )
    (net (code "17") (name "Net-(ICH1A-SCL)") (class "Default")
      (node (ref "ICH1") (pin "10") (pinfunction "SCL_10") (pintype "input"))
      (node (ref "R138") (pin "P$2") (pinfunction "2_P$2") (pintype "passive"))
    )
    (net (code "18") (name "Net-(ICH1A-SER)") (class "Default")
      (node (ref "ICH1") (pin "14") (pinfunction "SER_14") (pintype "input"))
      (node (ref "R163") (pin "P$2") (pinfunction "2_P$2") (pintype "passive"))
    )
    (net (code "19") (name "Net-(ICH2A-G)") (class "Default")
      (node (ref "ICH2") (pin "13") (pinfunction "G_13") (pintype "input"))
      (node (ref "R141") (pin "P$2") (pinfunction "2_P$2") (pintype "passive"))
    )
    (net (code "20") (name "Net-(ICH2A-QA)") (class "Default")
      (node (ref "ICH2") (pin "15") (pinfunction "QA_15") (pintype "tri_state"))
      (node (ref "R69") (pin "P$1") (pinfunction "1_P$1") (pintype "passive"))
    )
    (net (code "21") (name "Net-(ICH2A-QB)") (class "Default")
      (node (ref "ICH2") (pin "1") (pinfunction "QB_1") (pintype "tri_state"))
      (node (ref "R70") (pin "P$1") (pinfunction "1_P$1") (pintype "passive"))
    )
    (net (code "22") (name "Net-(ICH2A-QC)") (class "Default")
      (node (ref "ICH2") (pin "2") (pinfunction "QC_2") (pintype "tri_state"))
      (node (ref "R71") (pin "P$1") (pinfunction "1_P$1") (pintype "passive"))
    )
    (net (code "23") (name "Net-(ICH2A-QD)") (class "Default")
      (node (ref "ICH2") (pin "3") (pinfunction "QD_3") (pintype "tri_state"))
      (node (ref "R72") (pin "P$1") (pinfunction "1_P$1") (pintype "passive"))
    )
    (net (code "24") (name "Net-(ICH2A-QE)") (class "Default")
      (node (ref "ICH2") (pin "4") (pinfunction "QE_4") (pintype "tri_state"))
      (node (ref "R73") (pin "P$1") (pinfunction "1_P$1") (pintype "passive"))
    )
    (net (code "25") (name "Net-(ICH2A-QF)") (class "Default")
      (node (ref "ICH2") (pin "5") (pinfunction "QF_5") (pintype "tri_state"))
      (node (ref "R74") (pin "P$1") (pinfunction "1_P$1") (pintype "passive"))
    )
    (net (code "26") (name "Net-(ICH2A-QG)") (class "Default")
      (node (ref "ICH2") (pin "6") (pinfunction "QG_6") (pintype "tri_state"))
      (node (ref "R75") (pin "P$1") (pinfunction "1_P$1") (pintype "passive"))
    )
    (net (code "27") (name "Net-(ICH2A-QH)") (class "Default")
      (node (ref "ICH2") (pin "7") (pinfunction "QH_7") (pintype "tri_state"))
      (node (ref "R76") (pin "P$1") (pinfunction "1_P$1") (pintype "passive"))
    )
    (net (code "28") (name "Net-(ICH2A-QH*)") (class "Default")
      (node (ref "ICH2") (pin "9") (pinfunction "QH*_9") (pintype "tri_state"))
      (node (ref "ICH3") (pin "14") (pinfunction "SER_14") (pintype "input"))
    )
    (net (code "29") (name "Net-(ICH2A-SCL)") (class "Default")
      (node (ref "ICH2") (pin "10") (pinfunction "SCL_10") (pintype "input"))
      (node (ref "R140") (pin "P$2") (pinfunction "2_P$2") (pintype "passive"))
    )
    (net (code "30") (name "Net-(ICH3A-G)") (class "Default")
      (node (ref "ICH3") (pin "13") (pinfunction "G_13") (pintype "input"))
      (node (ref "R143") (pin "P$2") (pinfunction "2_P$2") (pintype "passive"))
    )
    (net (code "31") (name "Net-(ICH3A-QA)") (class "Default")
      (node (ref "ICH3") (pin "15") (pinfunction "QA_15") (pintype "tri_state"))
      (node (ref "R77") (pin "P$1") (pinfunction "1_P$1") (pintype "passive"))
    )
    (net (code "32") (name "Net-(ICH3A-QB)") (class "Default")
      (node (ref "ICH3") (pin "1") (pinfunction "QB_1") (pintype "tri_state"))
      (node (ref "R78") (pin "P$1") (pinfunction "1_P$1") (pintype "passive"))
    )
    (net (code "33") (name "Net-(ICH3A-QC)") (class "Default")
      (node (ref "ICH3") (pin "2") (pinfunction "QC_2") (pintype "tri_state"))
      (node (ref "R79") (pin "P$1") (pinfunction "1_P$1") (pintype "passive"))
    )
    (net (code "34") (name "Net-(ICH3A-QD)") (class "Default")
      (node (ref "ICH3") (pin "3") (pinfunction "QD_3") (pintype "tri_state"))
      (node (ref "R80") (pin "P$1") (pinfunction "1_P$1") (pintype "passive"))
    )
    (net (code "35") (name "Net-(ICH3A-QE)") (class "Default")
      (node (ref "ICH3") (pin "4") (pinfunction "QE_4") (pintype "tri_state"))
      (node (ref "R81") (pin "P$1") (pinfunction "1_P$1") (pintype "passive"))
    )
    (net (code "36") (name "Net-(ICH3A-QF)") (class "Default")
      (node (ref "ICH3") (pin "5") (pinfunction "QF_5") (pintype "tri_state"))
      (node (ref "R82") (pin "P$1") (pinfunction "1_P$1") (pintype "passive"))
    )
    (net (code "37") (name "Net-(ICH3A-QG)") (class "Default")
      (node (ref "ICH3") (pin "6") (pinfunction "QG_6") (pintype "tri_state"))
      (node (ref "R83") (pin "P$1") (pinfunction "1_P$1") (pintype "passive"))
    )
    (net (code "38") (name "Net-(ICH3A-QH)") (class "Default")
      (node (ref "ICH3") (pin "7") (pinfunction "QH_7") (pintype "tri_state"))
      (node (ref "R84") (pin "P$1") (pinfunction "1_P$1") (pintype "passive"))
    )
    (net (code "39") (name "Net-(ICH3A-SCL)") (class "Default")
      (node (ref "ICH3") (pin "10") (pinfunction "SCL_10") (pintype "input"))
      (node (ref "R142") (pin "P$2") (pinfunction "2_P$2") (pintype "passive"))
    )
    (net (code "40") (name "Net-(ICL1A-G)") (class "Default")
      (node (ref "ICL1") (pin "13") (pinfunction "G_13") (pintype "input"))
      (node (ref "R145") (pin "P$2") (pinfunction "2_P$2") (pintype "passive"))
    )
    (net (code "41") (name "Net-(ICL1A-QA)") (class "Default")
      (node (ref "ICL1") (pin "15") (pinfunction "QA_15") (pintype "tri_state"))
      (node (ref "R1") (pin "P$1") (pinfunction "1_P$1") (pintype "passive"))
    )
    (net (code "42") (name "Net-(ICL1A-QB)") (class "Default")
      (node (ref "ICL1") (pin "1") (pinfunction "QB_1") (pintype "tri_state"))
      (node (ref "R2") (pin "P$1") (pinfunction "1_P$1") (pintype "passive"))
    )
    (net (code "43") (name "Net-(ICL1A-QC)") (class "Default")
      (node (ref "ICL1") (pin "2") (pinfunction "QC_2") (pintype "tri_state"))
      (node (ref "R3") (pin "P$1") (pinfunction "1_P$1") (pintype "passive"))
    )
    (net (code "44") (name "Net-(ICL1A-QD)") (class "Default")
      (node (ref "ICL1") (pin "3") (pinfunction "QD_3") (pintype "tri_state"))
      (node (ref "R4") (pin "P$1") (pinfunction "1_P$1") (pintype "passive"))
    )
    (net (code "45") (name "Net-(ICL1A-QE)") (class "Default")
      (node (ref "ICL1") (pin "4") (pinfunction "QE_4") (pintype "tri_state"))
      (node (ref "R5") (pin "P$1") (pinfunction "1_P$1") (pintype "passive"))
    )
    (net (code "46") (name "Net-(ICL1A-QF)") (class "Default")
      (node (ref "ICL1") (pin "5") (pinfunction "QF_5") (pintype "tri_state"))
      (node (ref "R6") (pin "P$1") (pinfunction "1_P$1") (pintype "passive"))
    )
    (net (code "47") (name "Net-(ICL1A-QG)") (class "Default")
      (node (ref "ICL1") (pin "6") (pinfunction "QG_6") (pintype "tri_state"))
      (node (ref "R7") (pin "P$1") (pinfunction "1_P$1") (pintype "passive"))
    )
    (net (code "48") (name "Net-(ICL1A-QH)") (class "Default")
      (node (ref "ICL1") (pin "7") (pinfunction "QH_7") (pintype "tri_state"))
      (node (ref "R8") (pin "P$1") (pinfunction "1_P$1") (pintype "passive"))
    )
    (net (code "49") (name "Net-(ICL1A-QH*)") (class "Default")
      (node (ref "ICL1") (pin "9") (pinfunction "QH*_9") (pintype "tri_state"))
      (node (ref "ICL2") (pin "14") (pinfunction "SER_14") (pintype "input"))
    )
    (net (code "50") (name "Net-(ICL1A-RCK)") (class "Default")
      (node (ref "ICL1") (pin "12") (pinfunction "RCK_12") (pintype "input"))
      (node (ref "ICL2") (pin "12") (pinfunction "RCK_12") (pintype "input"))
      (node (ref "ICL3") (pin "12") (pinfunction "RCK_12") (pintype "input"))
      (node (ref "ICL4") (pin "12") (pinfunction "RCK_12") (pintype "input"))
      (node (ref "ICL5") (pin "12") (pinfunction "RCK_12") (pintype "input"))
      (node (ref "ICL6") (pin "12") (pinfunction "RCK_12") (pintype "input"))
      (node (ref "ICL7") (pin "12") (pinfunction "RCK_12") (pintype "input"))
      (node (ref "ICL8") (pin "12") (pinfunction "RCK_12") (pintype "input"))
      (node (ref "R161") (pin "P$2") (pinfunction "2_P$2") (pintype "passive"))
    )
    (net (code "51") (name "Net-(ICL1A-SCK)") (class "Default")
      (node (ref "ICL1") (pin "11") (pinfunction "SCK_11") (pintype "input"))
      (node (ref "ICL2") (pin "11") (pinfunction "SCK_11") (pintype "input"))
      (node (ref "ICL3") (pin "11") (pinfunction "SCK_11") (pintype "input"))
      (node (ref "ICL4") (pin "11") (pinfunction "SCK_11") (pintype "input"))
      (node (ref "ICL5") (pin "11") (pinfunction "SCK_11") (pintype "input"))
      (node (ref "ICL6") (pin "11") (pinfunction "SCK_11") (pintype "input"))
      (node (ref "ICL7") (pin "11") (pinfunction "SCK_11") (pintype "input"))
      (node (ref "ICL8") (pin "11") (pinfunction "SCK_11") (pintype "input"))
      (node (ref "R162") (pin "P$2") (pinfunction "2_P$2") (pintype "passive"))
    )
    (net (code "52") (name "Net-(ICL1A-SCL)") (class "Default")
      (node (ref "ICL1") (pin "10") (pinfunction "SCL_10") (pintype "input"))
      (node (ref "R144") (pin "P$2") (pinfunction "2_P$2") (pintype "passive"))
    )
    (net (code "53") (name "Net-(ICL1A-SER)") (class "Default")
      (node (ref "ICL1") (pin "14") (pinfunction "SER_14") (pintype "input"))
      (node (ref "R160") (pin "P$2") (pinfunction "2_P$2") (pintype "passive"))
    )
    (net (code "54") (name "Net-(ICL2A-G)") (class "Default")
      (node (ref "ICL2") (pin "13") (pinfunction "G_13") (pintype "input"))
      (node (ref "R147") (pin "P$2") (pinfunction "2_P$2") (pintype "passive"))
    )
    (net (code "55") (name "Net-(ICL2A-QA)") (class "Default")
      (node (ref "ICL2") (pin "15") (pinfunction "QA_15") (pintype "tri_state"))
      (node (ref "R9") (pin "P$1") (pinfunction "1_P$1") (pintype "passive"))
    )
    (net (code "56") (name "Net-(ICL2A-QB)") (class "Default")
      (node (ref "ICL2") (pin "1") (pinfunction "QB_1") (pintype "tri_state"))
      (node (ref "R10") (pin "P$1") (pinfunction "1_P$1") (pintype "passive"))
    )
    (net (code "57") (name "Net-(ICL2A-QC)") (class "Default")
      (node (ref "ICL2") (pin "2") (pinfunction "QC_2") (pintype "tri_state"))
      (node (ref "R11") (pin "P$1") (pinfunction "1_P$1") (pintype "passive"))
    )
    (net (code "58") (name "Net-(ICL2A-QD)") (class "Default")
      (node (ref "ICL2") (pin "3") (pinfunction "QD_3") (pintype "tri_state"))
      (node (ref "R12") (pin "P$1") (pinfunction "1_P$1") (pintype "passive"))
    )
    (net (code "59") (name "Net-(ICL2A-QE)") (class "Default")
      (node (ref "ICL2") (pin "4") (pinfunction "QE_4") (pintype "tri_state"))
      (node (ref "R13") (pin "P$1") (pinfunction "1_P$1") (pintype "passive"))
    )
    (net (code "60") (name "Net-(ICL2A-QF)") (class "Default")
      (node (ref "ICL2") (pin "5") (pinfunction "QF_5") (pintype "tri_state"))
      (node (ref "R14") (pin "P$1") (pinfunction "1_P$1") (pintype "passive"))
    )
    (net (code "61") (name "Net-(ICL2A-QG)") (class "Default")
      (node (ref "ICL2") (pin "6") (pinfunction "QG_6") (pintype "tri_state"))
      (node (ref "R15") (pin "P$1") (pinfunction "1_P$1") (pintype "passive"))
    )
    (net (code "62") (name "Net-(ICL2A-QH)") (class "Default")
      (node (ref "ICL2") (pin "7") (pinfunction "QH_7") (pintype "tri_state"))
      (node (ref "R16") (pin "P$1") (pinfunction "1_P$1") (pintype "passive"))
    )
    (net (code "63") (name "Net-(ICL2A-QH*)") (class "Default")
      (node (ref "ICL2") (pin "9") (pinfunction "QH*_9") (pintype "tri_state"))
      (node (ref "ICL3") (pin "14") (pinfunction "SER_14") (pintype "input"))
    )
    (net (code "64") (name "Net-(ICL2A-SCL)") (class "Default")
      (node (ref "ICL2") (pin "10") (pinfunction "SCL_10") (pintype "input"))
      (node (ref "R146") (pin "P$2") (pinfunction "2_P$2") (pintype "passive"))
    )
    (net (code "65") (name "Net-(ICL3A-G)") (class "Default")
      (node (ref "ICL3") (pin "13") (pinfunction "G_13") (pintype "input"))
      (node (ref "R149") (pin "P$2") (pinfunction "2_P$2") (pintype "passive"))
    )
    (net (code "66") (name "Net-(ICL3A-QA)") (class "Default")
      (node (ref "ICL3") (pin "15") (pinfunction "QA_15") (pintype "tri_state"))
      (node (ref "R17") (pin "P$1") (pinfunction "1_P$1") (pintype "passive"))
    )
    (net (code "67") (name "Net-(ICL3A-QB)") (class "Default")
      (node (ref "ICL3") (pin "1") (pinfunction "QB_1") (pintype "tri_state"))
      (node (ref "R18") (pin "P$1") (pinfunction "1_P$1") (pintype "passive"))
    )
    (net (code "68") (name "Net-(ICL3A-QC)") (class "Default")
      (node (ref "ICL3") (pin "2") (pinfunction "QC_2") (pintype "tri_state"))
      (node (ref "R19") (pin "P$1") (pinfunction "1_P$1") (pintype "passive"))
    )
    (net (code "69") (name "Net-(ICL3A-QD)") (class "Default")
      (node (ref "ICL3") (pin "3") (pinfunction "QD_3") (pintype "tri_state"))
      (node (ref "R20") (pin "P$1") (pinfunction "1_P$1") (pintype "passive"))
    )
    (net (code "70") (name "Net-(ICL3A-QE)") (class "Default")
      (node (ref "ICL3") (pin "4") (pinfunction "QE_4") (pintype "tri_state"))
      (node (ref "R21") (pin "P$1") (pinfunction "1_P$1") (pintype "passive"))
    )
    (net (code "71") (name "Net-(ICL3A-QF)") (class "Default")
      (node (ref "ICL3") (pin "5") (pinfunction "QF_5") (pintype "tri_state"))
      (node (ref "R22") (pin "P$1") (pinfunction "1_P$1") (pintype "passive"))
    )
    (net (code "72") (name "Net-(ICL3A-QG)") (class "Default")
      (node (ref "ICL3") (pin "6") (pinfunction "QG_6") (pintype "tri_state"))
      (node (ref "R23") (pin "P$1") (pinfunction "1_P$1") (pintype "passive"))
    )
    (net (code "73") (name "Net-(ICL3A-QH)") (class "Default")
      (node (ref "ICL3") (pin "7") (pinfunction "QH_7") (pintype "tri_state"))
      (node (ref "R24") (pin "P$1") (pinfunction "1_P$1") (pintype "passive"))
    )
    (net (code "74") (name "Net-(ICL3A-QH*)") (class "Default")
      (node (ref "ICL3") (pin "9") (pinfunction "QH*_9") (pintype "tri_state"))
      (node (ref "ICL4") (pin "14") (pinfunction "SER_14") (pintype "input"))
    )
    (net (code "75") (name "Net-(ICL3A-SCL)") (class "Default")
      (node (ref "ICL3") (pin "10") (pinfunction "SCL_10") (pintype "input"))
      (node (ref "R148") (pin "P$2") (pinfunction "2_P$2") (pintype "passive"))
    )
    (net (code "76") (name "Net-(ICL4A-G)") (class "Default")
      (node (ref "ICL4") (pin "13") (pinfunction "G_13") (pintype "input"))
      (node (ref "R151") (pin "P$2") (pinfunction "2_P$2") (pintype "passive"))
    )
    (net (code "77") (name "Net-(ICL4A-QA)") (class "Default")
      (node (ref "ICL4") (pin "15") (pinfunction "QA_15") (pintype "tri_state"))
      (node (ref "R25") (pin "P$1") (pinfunction "1_P$1") (pintype "passive"))
    )
    (net (code "78") (name "Net-(ICL4A-QB)") (class "Default")
      (node (ref "ICL4") (pin "1") (pinfunction "QB_1") (pintype "tri_state"))
      (node (ref "R26") (pin "P$1") (pinfunction "1_P$1") (pintype "passive"))
    )
    (net (code "79") (name "Net-(ICL4A-QC)") (class "Default")
      (node (ref "ICL4") (pin "2") (pinfunction "QC_2") (pintype "tri_state"))
      (node (ref "R27") (pin "P$1") (pinfunction "1_P$1") (pintype "passive"))
    )
    (net (code "80") (name "Net-(ICL4A-QD)") (class "Default")
      (node (ref "ICL4") (pin "3") (pinfunction "QD_3") (pintype "tri_state"))
      (node (ref "R28") (pin "P$1") (pinfunction "1_P$1") (pintype "passive"))
    )
    (net (code "81") (name "Net-(ICL4A-QE)") (class "Default")
      (node (ref "ICL4") (pin "4") (pinfunction "QE_4") (pintype "tri_state"))
      (node (ref "R29") (pin "P$1") (pinfunction "1_P$1") (pintype "passive"))
    )
    (net (code "82") (name "Net-(ICL4A-QF)") (class "Default")
      (node (ref "ICL4") (pin "5") (pinfunction "QF_5") (pintype "tri_state"))
      (node (ref "R30") (pin "P$1") (pinfunction "1_P$1") (pintype "passive"))
    )
    (net (code "83") (name "Net-(ICL4A-QG)") (class "Default")
      (node (ref "ICL4") (pin "6") (pinfunction "QG_6") (pintype "tri_state"))
      (node (ref "R31") (pin "P$1") (pinfunction "1_P$1") (pintype "passive"))
    )
    (net (code "84") (name "Net-(ICL4A-QH)") (class "Default")
      (node (ref "ICL4") (pin "7") (pinfunction "QH_7") (pintype "tri_state"))
      (node (ref "R32") (pin "P$1") (pinfunction "1_P$1") (pintype "passive"))
    )
    (net (code "85") (name "Net-(ICL4A-QH*)") (class "Default")
      (node (ref "ICL4") (pin "9") (pinfunction "QH*_9") (pintype "tri_state"))
      (node (ref "ICL5") (pin "14") (pinfunction "SER_14") (pintype "input"))
    )
    (net (code "86") (name "Net-(ICL4A-SCL)") (class "Default")
      (node (ref "ICL4") (pin "10") (pinfunction "SCL_10") (pintype "input"))
      (node (ref "R150") (pin "P$2") (pinfunction "2_P$2") (pintype "passive"))
    )
    (net (code "87") (name "Net-(ICL5A-G)") (class "Default")
      (node (ref "ICL5") (pin "13") (pinfunction "G_13") (pintype "input"))
      (node (ref "R153") (pin "P$2") (pinfunction "2_P$2") (pintype "passive"))
    )
    (net (code "88") (name "Net-(ICL5A-QA)") (class "Default")
      (node (ref "ICL5") (pin "15") (pinfunction "QA_15") (pintype "tri_state"))
      (node (ref "R33") (pin "P$1") (pinfunction "1_P$1") (pintype "passive"))
    )
    (net (code "89") (name "Net-(ICL5A-QB)") (class "Default")
      (node (ref "ICL5") (pin "1") (pinfunction "QB_1") (pintype "tri_state"))
      (node (ref "R34") (pin "P$1") (pinfunction "1_P$1") (pintype "passive"))
    )
    (net (code "90") (name "Net-(ICL5A-QC)") (class "Default")
      (node (ref "ICL5") (pin "2") (pinfunction "QC_2") (pintype "tri_state"))
      (node (ref "R35") (pin "P$1") (pinfunction "1_P$1") (pintype "passive"))
    )
    (net (code "91") (name "Net-(ICL5A-QD)") (class "Default")
      (node (ref "ICL5") (pin "3") (pinfunction "QD_3") (pintype "tri_state"))
      (node (ref "R36") (pin "P$1") (pinfunction "1_P$1") (pintype "passive"))
    )
    (net (code "92") (name "Net-(ICL5A-QE)") (class "Default")
      (node (ref "ICL5") (pin "4") (pinfunction "QE_4") (pintype "tri_state"))
      (node (ref "R37") (pin "P$1") (pinfunction "1_P$1") (pintype "passive"))
    )
    (net (code "93") (name "Net-(ICL5A-QF)") (class "Default")
      (node (ref "ICL5") (pin "5") (pinfunction "QF_5") (pintype "tri_state"))
      (node (ref "R38") (pin "P$1") (pinfunction "1_P$1") (pintype "passive"))
    )
    (net (code "94") (name "Net-(ICL5A-QG)") (class "Default")
      (node (ref "ICL5") (pin "6") (pinfunction "QG_6") (pintype "tri_state"))
      (node (ref "R39") (pin "P$1") (pinfunction "1_P$1") (pintype "passive"))
    )
    (net (code "95") (name "Net-(ICL5A-QH)") (class "Default")
      (node (ref "ICL5") (pin "7") (pinfunction "QH_7") (pintype "tri_state"))
      (node (ref "R40") (pin "P$1") (pinfunction "1_P$1") (pintype "passive"))
    )
    (net (code "96") (name "Net-(ICL5A-QH*)") (class "Default")
      (node (ref "ICL5") (pin "9") (pinfunction "QH*_9") (pintype "tri_state"))
      (node (ref "ICL6") (pin "14") (pinfunction "SER_14") (pintype "input"))
    )
    (net (code "97") (name "Net-(ICL5A-SCL)") (class "Default")
      (node (ref "ICL5") (pin "10") (pinfunction "SCL_10") (pintype "input"))
      (node (ref "R152") (pin "P$2") (pinfunction "2_P$2") (pintype "passive"))
    )
    (net (code "98") (name "Net-(ICL6A-G)") (class "Default")
      (node (ref "ICL6") (pin "13") (pinfunction "G_13") (pintype "input"))
      (node (ref "R155") (pin "P$2") (pinfunction "2_P$2") (pintype "passive"))
    )
    (net (code "99") (name "Net-(ICL6A-QA)") (class "Default")
      (node (ref "ICL6") (pin "15") (pinfunction "QA_15") (pintype "tri_state"))
      (node (ref "R41") (pin "P$1") (pinfunction "1_P$1") (pintype "passive"))
    )
    (net (code "100") (name "Net-(ICL6A-QB)") (class "Default")
      (node (ref "ICL6") (pin "1") (pinfunction "QB_1") (pintype "tri_state"))
      (node (ref "R42") (pin "P$1") (pinfunction "1_P$1") (pintype "passive"))
    )
    (net (code "101") (name "Net-(ICL6A-QC)") (class "Default")
      (node (ref "ICL6") (pin "2") (pinfunction "QC_2") (pintype "tri_state"))
      (node (ref "R43") (pin "P$1") (pinfunction "1_P$1") (pintype "passive"))
    )
    (net (code "102") (name "Net-(ICL6A-QD)") (class "Default")
      (node (ref "ICL6") (pin "3") (pinfunction "QD_3") (pintype "tri_state"))
      (node (ref "R44") (pin "P$1") (pinfunction "1_P$1") (pintype "passive"))
    )
    (net (code "103") (name "Net-(ICL6A-QE)") (class "Default")
      (node (ref "ICL6") (pin "4") (pinfunction "QE_4") (pintype "tri_state"))
      (node (ref "R45") (pin "P$1") (pinfunction "1_P$1") (pintype "passive"))
    )
    (net (code "104") (name "Net-(ICL6A-QF)") (class "Default")
      (node (ref "ICL6") (pin "5") (pinfunction "QF_5") (pintype "tri_state"))
      (node (ref "R46") (pin "P$1") (pinfunction "1_P$1") (pintype "passive"))
    )
    (net (code "105") (name "Net-(ICL6A-QG)") (class "Default")
      (node (ref "ICL6") (pin "6") (pinfunction "QG_6") (pintype "tri_state"))
      (node (ref "R47") (pin "P$1") (pinfunction "1_P$1") (pintype "passive"))
    )
    (net (code "106") (name "Net-(ICL6A-QH)") (class "Default")
      (node (ref "ICL6") (pin "7") (pinfunction "QH_7") (pintype "tri_state"))
      (node (ref "R48") (pin "P$1") (pinfunction "1_P$1") (pintype "passive"))
    )
    (net (code "107") (name "Net-(ICL6A-QH*)") (class "Default")
      (node (ref "ICL6") (pin "9") (pinfunction "QH*_9") (pintype "tri_state"))
      (node (ref "ICL7") (pin "14") (pinfunction "SER_14") (pintype "input"))
    )
    (net (code "108") (name "Net-(ICL6A-SCL)") (class "Default")
      (node (ref "ICL6") (pin "10") (pinfunction "SCL_10") (pintype "input"))
      (node (ref "R154") (pin "P$2") (pinfunction "2_P$2") (pintype "passive"))
    )
    (net (code "109") (name "Net-(ICL7A-G)") (class "Default")
      (node (ref "ICL7") (pin "13") (pinfunction "G_13") (pintype "input"))
      (node (ref "R157") (pin "P$2") (pinfunction "2_P$2") (pintype "passive"))
    )
    (net (code "110") (name "Net-(ICL7A-QA)") (class "Default")
      (node (ref "ICL7") (pin "15") (pinfunction "QA_15") (pintype "tri_state"))
      (node (ref "R49") (pin "P$1") (pinfunction "1_P$1") (pintype "passive"))
    )
    (net (code "111") (name "Net-(ICL7A-QB)") (class "Default")
      (node (ref "ICL7") (pin "1") (pinfunction "QB_1") (pintype "tri_state"))
      (node (ref "R50") (pin "P$1") (pinfunction "1_P$1") (pintype "passive"))
    )
    (net (code "112") (name "Net-(ICL7A-QC)") (class "Default")
      (node (ref "ICL7") (pin "2") (pinfunction "QC_2") (pintype "tri_state"))
      (node (ref "R51") (pin "P$1") (pinfunction "1_P$1") (pintype "passive"))
    )
    (net (code "113") (name "Net-(ICL7A-QD)") (class "Default")
      (node (ref "ICL7") (pin "3") (pinfunction "QD_3") (pintype "tri_state"))
      (node (ref "R52") (pin "P$1") (pinfunction "1_P$1") (pintype "passive"))
    )
    (net (code "114") (name "Net-(ICL7A-QE)") (class "Default")
      (node (ref "ICL7") (pin "4") (pinfunction "QE_4") (pintype "tri_state"))
      (node (ref "R53") (pin "P$1") (pinfunction "1_P$1") (pintype "passive"))
    )
    (net (code "115") (name "Net-(ICL7A-QF)") (class "Default")
      (node (ref "ICL7") (pin "5") (pinfunction "QF_5") (pintype "tri_state"))
      (node (ref "R54") (pin "P$1") (pinfunction "1_P$1") (pintype "passive"))
    )
    (net (code "116") (name "Net-(ICL7A-QG)") (class "Default")
      (node (ref "ICL7") (pin "6") (pinfunction "QG_6") (pintype "tri_state"))
      (node (ref "R55") (pin "P$1") (pinfunction "1_P$1") (pintype "passive"))
    )
    (net (code "117") (name "Net-(ICL7A-QH)") (class "Default")
      (node (ref "ICL7") (pin "7") (pinfunction "QH_7") (pintype "tri_state"))
      (node (ref "R56") (pin "P$1") (pinfunction "1_P$1") (pintype "passive"))
    )
    (net (code "118") (name "Net-(ICL7A-QH*)") (class "Default")
      (node (ref "ICL7") (pin "9") (pinfunction "QH*_9") (pintype "tri_state"))
      (node (ref "ICL8") (pin "14") (pinfunction "SER_14") (pintype "input"))
    )
    (net (code "119") (name "Net-(ICL7A-SCL)") (class "Default")
      (node (ref "ICL7") (pin "10") (pinfunction "SCL_10") (pintype "input"))
      (node (ref "R156") (pin "P$2") (pinfunction "2_P$2") (pintype "passive"))
    )
    (net (code "120") (name "Net-(ICL8A-G)") (class "Default")
      (node (ref "ICL8") (pin "13") (pinfunction "G_13") (pintype "input"))
      (node (ref "R159") (pin "P$2") (pinfunction "2_P$2") (pintype "passive"))
    )
    (net (code "121") (name "Net-(ICL8A-QA)") (class "Default")
      (node (ref "ICL8") (pin "15") (pinfunction "QA_15") (pintype "tri_state"))
      (node (ref "R57") (pin "P$1") (pinfunction "1_P$1") (pintype "passive"))
    )
    (net (code "122") (name "Net-(ICL8A-QB)") (class "Default")
      (node (ref "ICL8") (pin "1") (pinfunction "QB_1") (pintype "tri_state"))
      (node (ref "R58") (pin "P$1") (pinfunction "1_P$1") (pintype "passive"))
    )
    (net (code "123") (name "Net-(ICL8A-QC)") (class "Default")
      (node (ref "ICL8") (pin "2") (pinfunction "QC_2") (pintype "tri_state"))
      (node (ref "R59") (pin "P$1") (pinfunction "1_P$1") (pintype "passive"))
    )
    (net (code "124") (name "Net-(ICL8A-QD)") (class "Default")
      (node (ref "ICL8") (pin "3") (pinfunction "QD_3") (pintype "tri_state"))
      (node (ref "R60") (pin "P$1") (pinfunction "1_P$1") (pintype "passive"))
    )
    (net (code "125") (name "Net-(ICL8A-SCL)") (class "Default")
      (node (ref "ICL8") (pin "10") (pinfunction "SCL_10") (pintype "input"))
      (node (ref "R158") (pin "P$2") (pinfunction "2_P$2") (pintype "passive"))
    )
    (net (code "126") (name "Net-(M1-A0)") (class "Default")
      (node (ref "M1") (pin "J2.12") (pinfunction "A0_J2.12") (pintype "bidirectional"))
      (node (ref "R164") (pin "P$2") (pinfunction "2_P$2") (pintype "passive"))
    )
    (net (code "127") (name "Net-(M1-A1)") (class "Default")
      (node (ref "M1") (pin "J2.11") (pinfunction "A1_J2.11") (pintype "bidirectional"))
      (node (ref "R128") (pin "P$2") (pinfunction "2_P$2") (pintype "passive"))
    )
    (net (code "128") (name "Net-(M1-A2)") (class "Default")
      (node (ref "M1") (pin "J2.10") (pinfunction "A2_J2.10") (pintype "bidirectional"))
      (node (ref "R129") (pin "P$2") (pinfunction "2_P$2") (pintype "passive"))
    )
    (net (code "129") (name "Net-(M1-A3)") (class "Default")
      (node (ref "M1") (pin "J2.9") (pinfunction "A3_J2.9") (pintype "bidirectional"))
      (node (ref "R127") (pin "P$2") (pinfunction "2_P$2") (pintype "passive"))
    )
    (net (code "130") (name "Net-(M1-A4)") (class "Default")
      (node (ref "M1") (pin "J2.8") (pinfunction "A4_J2.8") (pintype "bidirectional"))
      (node (ref "U$1") (pin "J1.3") (pinfunction "SDA.1_J1.3") (pintype "bidirectional"))
    )
    (net (code "131") (name "Net-(M1-A5)") (class "Default")
      (node (ref "M1") (pin "J2.7") (pinfunction "A5_J2.7") (pintype "bidirectional"))
      (node (ref "U$1") (pin "J1.4") (pinfunction "SCL.1_J1.4") (pintype "bidirectional"))
    )
    (net (code "132") (name "Net-(M1-D2)") (class "Default")
      (node (ref "M1") (pin "J1.5") (pinfunction "D2_J1.5") (pintype "bidirectional"))
      (node (ref "R161") (pin "P$1") (pinfunction "1_P$1") (pintype "passive"))
    )
    (net (code "133") (name "Net-(M1-D3)") (class "Default")
      (node (ref "M1") (pin "J1.6") (pinfunction "D3_J1.6") (pintype "bidirectional"))
      (node (ref "R162") (pin "P$1") (pinfunction "1_P$1") (pintype "passive"))
    )
    (net (code "134") (name "Net-(M1-D4)") (class "Default")
      (node (ref "M1") (pin "J1.7") (pinfunction "D4_J1.7") (pintype "bidirectional"))
      (node (ref "R160") (pin "P$1") (pinfunction "1_P$1") (pintype "passive"))
    )
    (net (code "135") (name "Net-(M1-D5)") (class "Default")
      (node (ref "J1") (pin "7") (pinfunction "7_7") (pintype "passive"))
      (node (ref "M1") (pin "J1.8") (pinfunction "D5_J1.8") (pintype "bidirectional"))
    )
    (net (code "136") (name "Net-(M1-D6)") (class "Default")
      (node (ref "J1") (pin "6") (pinfunction "6_6") (pintype "passive"))
      (node (ref "M1") (pin "J1.9") (pinfunction "D6_J1.9") (pintype "bidirectional"))
    )
    (net (code "137") (name "Net-(M1-D7)") (class "Default")
      (node (ref "J1") (pin "5") (pinfunction "5_5") (pintype "passive"))
      (node (ref "M1") (pin "J1.10") (pinfunction "D7_J1.10") (pintype "bidirectional"))
    )
    (net (code "138") (name "Net-(M1-D8)") (class "Default")
      (node (ref "J1") (pin "4") (pinfunction "4_4") (pintype "passive"))
      (node (ref "M1") (pin "J1.11") (pinfunction "D8_J1.11") (pintype "bidirectional"))
    )
    (net (code "139") (name "Net-(M1-D9)") (class "Default")
      (node (ref "J1") (pin "3") (pinfunction "3_3") (pintype "passive"))
      (node (ref "M1") (pin "J1.12") (pinfunction "D9_J1.12") (pintype "bidirectional"))
    )
    (net (code "140") (name "Net-(M1-D10)") (class "Default")
      (node (ref "J1") (pin "2") (pinfunction "2_2") (pintype "passive"))
      (node (ref "M1") (pin "J1.13") (pinfunction "D10_J1.13") (pintype "bidirectional"))
    )
    (net (code "141") (name "Net-(M1-D11{slash}MOSI)") (class "Default")
      (node (ref "J1") (pin "1") (pinfunction "1_1") (pintype "passive"))
      (node (ref "M1") (pin "J1.14") (pinfunction "D11/MOSI_J1.14") (pintype "bidirectional"))
    )
    (net (code "142") (name "Net-(M1-D12{slash}MISO)") (class "Default")
      (node (ref "M1") (pin "J1.15") (pinfunction "D12/MISO_J1.15") (pintype "bidirectional"))
      (node (ref "R163") (pin "P$1") (pinfunction "1_P$1") (pintype "passive"))
    )
    (net (code "143") (name "Net-(M1-D13{slash}SCK)") (class "Default")
      (node (ref "M1") (pin "J2.15") (pinfunction "D13/SCK_J2.15") (pintype "bidirectional"))
      (node (ref "R165") (pin "P$2") (pinfunction "2_P$2") (pintype "passive"))
    )
    (net (code "144") (name "Net-(R1-2)") (class "Default")
      (node (ref "D1") (pin "A") (pinfunction "A_A") (pintype "passive"))
      (node (ref "R1") (pin "P$2") (pinfunction "2_P$2") (pintype "passive"))
    )
    (net (code "145") (name "Net-(R2-2)") (class "Default")
      (node (ref "D2") (pin "A") (pinfunction "A_A") (pintype "passive"))
      (node (ref "R2") (pin "P$2") (pinfunction "2_P$2") (pintype "passive"))
    )
    (net (code "146") (name "Net-(R3-2)") (class "Default")
      (node (ref "D3") (pin "A") (pinfunction "A_A") (pintype "passive"))
      (node (ref "R3") (pin "P$2") (pinfunction "2_P$2") (pintype "passive"))
    )
    (net (code "147") (name "Net-(R4-2)") (class "Default")
      (node (ref "D4") (pin "A") (pinfunction "A_A") (pintype "passive"))
      (node (ref "R4") (pin "P$2") (pinfunction "2_P$2") (pintype "passive"))
    )
    (net (code "148") (name "Net-(R5-2)") (class "Default")
      (node (ref "D5") (pin "A") (pinfunction "A_A") (pintype "passive"))
      (node (ref "R5") (pin "P$2") (pinfunction "2_P$2") (pintype "passive"))
    )
    (net (code "149") (name "Net-(R6-2)") (class "Default")
      (node (ref "D6") (pin "A") (pinfunction "A_A") (pintype "passive"))
      (node (ref "R6") (pin "P$2") (pinfunction "2_P$2") (pintype "passive"))
    )
    (net (code "150") (name "Net-(R7-2)") (class "Default")
      (node (ref "D7") (pin "A") (pinfunction "A_A") (pintype "passive"))
      (node (ref "R7") (pin "P$2") (pinfunction "2_P$2") (pintype "passive"))
    )
    (net (code "151") (name "Net-(R8-2)") (class "Default")
      (node (ref "D8") (pin "A") (pinfunction "A_A") (pintype "passive"))
      (node (ref "R8") (pin "P$2") (pinfunction "2_P$2") (pintype "passive"))
    )
    (net (code "152") (name "Net-(R9-2)") (class "Default")
      (node (ref "D9") (pin "A") (pinfunction "A_A") (pintype "passive"))
      (node (ref "R9") (pin "P$2") (pinfunction "2_P$2") (pintype "passive"))
    )
    (net (code "153") (name "Net-(R10-2)") (class "Default")
      (node (ref "D10") (pin "A") (pinfunction "A_A") (pintype "passive"))
      (node (ref "R10") (pin "P$2") (pinfunction "2_P$2") (pintype "passive"))
    )
    (net (code "154") (name "Net-(R11-2)") (class "Default")
      (node (ref "D11") (pin "A") (pinfunction "A_A") (pintype "passive"))
      (node (ref "R11") (pin "P$2") (pinfunction "2_P$2") (pintype "passive"))
    )
    (net (code "155") (name "Net-(R12-2)") (class "Default")
      (node (ref "D12") (pin "A") (pinfunction "A_A") (pintype "passive"))
      (node (ref "R12") (pin "P$2") (pinfunction "2_P$2") (pintype "passive"))
    )
    (net (code "156") (name "Net-(R13-2)") (class "Default")
      (node (ref "D13") (pin "A") (pinfunction "A_A") (pintype "passive"))
      (node (ref "R13") (pin "P$2") (pinfunction "2_P$2") (pintype "passive"))
    )
    (net (code "157") (name "Net-(R14-2)") (class "Default")
      (node (ref "D14") (pin "A") (pinfunction "A_A") (pintype "passive"))
      (node (ref "R14") (pin "P$2") (pinfunction "2_P$2") (pintype "passive"))
    )
    (net (code "158") (name "Net-(R15-2)") (class "Default")
      (node (ref "D15") (pin "A") (pinfunction "A_A") (pintype "passive"))
      (node (ref "R15") (pin "P$2") (pinfunction "2_P$2") (pintype "passive"))
    )
    (net (code "159") (name "Net-(R16-2)") (class "Default")
      (node (ref "D16") (pin "A") (pinfunction "A_A") (pintype "passive"))
      (node (ref "R16") (pin "P$2") (pinfunction "2_P$2") (pintype "passive"))
    )
    (net (code "160") (name "Net-(R17-2)") (class "Default")
      (node (ref "D17") (pin "A") (pinfunction "A_A") (pintype "passive"))
      (node (ref "R17") (pin "P$2") (pinfunction "2_P$2") (pintype "passive"))
    )
    (net (code "161") (name "Net-(R18-2)") (class "Default")
      (node (ref "D18") (pin "A") (pinfunction "A_A") (pintype "passive"))
      (node (ref "R18") (pin "P$2") (pinfunction "2_P$2") (pintype "passive"))
    )
    (net (code "162") (name "Net-(R19-2)") (class "Default")
      (node (ref "D19") (pin "A") (pinfunction "A_A") (pintype "passive"))
      (node (ref "R19") (pin "P$2") (pinfunction "2_P$2") (pintype "passive"))
    )
    (net (code "163") (name "Net-(R20-2)") (class "Default")
      (node (ref "D20") (pin "A") (pinfunction "A_A") (pintype "passive"))
      (node (ref "R20") (pin "P$2") (pinfunction "2_P$2") (pintype "passive"))
    )
    (net (code "164") (name "Net-(R21-2)") (class "Default")
      (node (ref "D21") (pin "A") (pinfunction "A_A") (pintype "passive"))
      (node (ref "R21") (pin "P$2") (pinfunction "2_P$2") (pintype "passive"))
    )
    (net (code "165") (name "Net-(R22-2)") (class "Default")
      (node (ref "D22") (pin "A") (pinfunction "A_A") (pintype "passive"))
      (node (ref "R22") (pin "P$2") (pinfunction "2_P$2") (pintype "passive"))
    )
    (net (code "166") (name "Net-(R23-2)") (class "Default")
      (node (ref "D23") (pin "A") (pinfunction "A_A") (pintype "passive"))
      (node (ref "R23") (pin "P$2") (pinfunction "2_P$2") (pintype "passive"))
    )
    (net (code "167") (name "Net-(R24-2)") (class "Default")
      (node (ref "D24") (pin "A") (pinfunction "A_A") (pintype "passive"))
      (node (ref "R24") (pin "P$2") (pinfunction "2_P$2") (pintype "passive"))
    )
    (net (code "168") (name "Net-(R25-2)") (class "Default")
      (node (ref "D25") (pin "A") (pinfunction "A_A") (pintype "passive"))
      (node (ref "R25") (pin "P$2") (pinfunction "2_P$2") (pintype "passive"))
    )
    (net (code "169") (name "Net-(R26-2)") (class "Default")
      (node (ref "D26") (pin "A") (pinfunction "A_A") (pintype "passive"))
      (node (ref "R26") (pin "P$2") (pinfunction "2_P$2") (pintype "passive"))
    )
    (net (code "170") (name "Net-(R27-2)") (class "Default")
      (node (ref "D27") (pin "A") (pinfunction "A_A") (pintype "passive"))
      (node (ref "R27") (pin "P$2") (pinfunction "2_P$2") (pintype "passive"))
    )
    (net (code "171") (name "Net-(R28-2)") (class "Default")
      (node (ref "D28") (pin "A") (pinfunction "A_A") (pintype "passive"))
      (node (ref "R28") (pin "P$2") (pinfunction "2_P$2") (pintype "passive"))
    )
    (net (code "172") (name "Net-(R29-2)") (class "Default")
      (node (ref "D29") (pin "A") (pinfunction "A_A") (pintype "passive"))
      (node (ref "R29") (pin "P$2") (pinfunction "2_P$2") (pintype "passive"))
    )
    (net (code "173") (name "Net-(R30-2)") (class "Default")
      (node (ref "D30") (pin "A") (pinfunction "A_A") (pintype "passive"))
      (node (ref "R30") (pin "P$2") (pinfunction "2_P$2") (pintype "passive"))
    )
    (net (code "174") (name "Net-(R31-2)") (class "Default")
      (node (ref "D31") (pin "A") (pinfunction "A_A") (pintype "passive"))
      (node (ref "R31") (pin "P$2") (pinfunction "2_P$2") (pintype "passive"))
    )
    (net (code "175") (name "Net-(R32-2)") (class "Default")
      (node (ref "D32") (pin "A") (pinfunction "A_A") (pintype "passive"))
      (node (ref "R32") (pin "P$2") (pinfunction "2_P$2") (pintype "passive"))
    )
    (net (code "176") (name "Net-(R33-2)") (class "Default")
      (node (ref "D33") (pin "A") (pinfunction "A_A") (pintype "passive"))
      (node (ref "R33") (pin "P$2") (pinfunction "2_P$2") (pintype "passive"))
    )
    (net (code "177") (name "Net-(R34-2)") (class "Default")
      (node (ref "D34") (pin "A") (pinfunction "A_A") (pintype "passive"))
      (node (ref "R34") (pin "P$2") (pinfunction "2_P$2") (pintype "passive"))
    )
    (net (code "178") (name "Net-(R35-2)") (class "Default")
      (node (ref "D35") (pin "A") (pinfunction "A_A") (pintype "passive"))
      (node (ref "R35") (pin "P$2") (pinfunction "2_P$2") (pintype "passive"))
    )
    (net (code "179") (name "Net-(R36-2)") (class "Default")
      (node (ref "D36") (pin "A") (pinfunction "A_A") (pintype "passive"))
      (node (ref "R36") (pin "P$2") (pinfunction "2_P$2") (pintype "passive"))
    )
    (net (code "180") (name "Net-(R37-2)") (class "Default")
      (node (ref "D37") (pin "A") (pinfunction "A_A") (pintype "passive"))
      (node (ref "R37") (pin "P$2") (pinfunction "2_P$2") (pintype "passive"))
    )
    (net (code "181") (name "Net-(R38-2)") (class "Default")
      (node (ref "D38") (pin "A") (pinfunction "A_A") (pintype "passive"))
      (node (ref "R38") (pin "P$2") (pinfunction "2_P$2") (pintype "passive"))
    )
    (net (code "182") (name "Net-(R39-2)") (class "Default")
      (node (ref "D39") (pin "A") (pinfunction "A_A") (pintype "passive"))
      (node (ref "R39") (pin "P$2") (pinfunction "2_P$2") (pintype "passive"))
    )
    (net (code "183") (name "Net-(R40-2)") (class "Default")
      (node (ref "D40") (pin "A") (pinfunction "A_A") (pintype "passive"))
      (node (ref "R40") (pin "P$2") (pinfunction "2_P$2") (pintype "passive"))
    )
    (net (code "184") (name "Net-(R41-2)") (class "Default")
      (node (ref "D41") (pin "A") (pinfunction "A_A") (pintype "passive"))
      (node (ref "R41") (pin "P$2") (pinfunction "2_P$2") (pintype "passive"))
    )
    (net (code "185") (name "Net-(R42-2)") (class "Default")
      (node (ref "D42") (pin "A") (pinfunction "A_A") (pintype "passive"))
      (node (ref "R42") (pin "P$2") (pinfunction "2_P$2") (pintype "passive"))
    )
    (net (code "186") (name "Net-(R43-2)") (class "Default")
      (node (ref "D43") (pin "A") (pinfunction "A_A") (pintype "passive"))
      (node (ref "R43") (pin "P$2") (pinfunction "2_P$2") (pintype "passive"))
    )
    (net (code "187") (name "Net-(R44-2)") (class "Default")
      (node (ref "D44") (pin "A") (pinfunction "A_A") (pintype "passive"))
      (node (ref "R44") (pin "P$2") (pinfunction "2_P$2") (pintype "passive"))
    )
    (net (code "188") (name "Net-(R45-2)") (class "Default")
      (node (ref "D45") (pin "A") (pinfunction "A_A") (pintype "passive"))
      (node (ref "R45") (pin "P$2") (pinfunction "2_P$2") (pintype "passive"))
    )
    (net (code "189") (name "Net-(R46-2)") (class "Default")
      (node (ref "D46") (pin "A") (pinfunction "A_A") (pintype "passive"))
      (node (ref "R46") (pin "P$2") (pinfunction "2_P$2") (pintype "passive"))
    )
    (net (code "190") (name "Net-(R47-2)") (class "Default")
      (node (ref "D47") (pin "A") (pinfunction "A_A") (pintype "passive"))
      (node (ref "R47") (pin "P$2") (pinfunction "2_P$2") (pintype "passive"))
    )
    (net (code "191") (name "Net-(R48-2)") (class "Default")
      (node (ref "D48") (pin "A") (pinfunction "A_A") (pintype "passive"))
      (node (ref "R48") (pin "P$2") (pinfunction "2_P$2") (pintype "passive"))
    )
    (net (code "192") (name "Net-(R49-2)") (class "Default")
      (node (ref "D49") (pin "A") (pinfunction "A_A") (pintype "passive"))
      (node (ref "R49") (pin "P$2") (pinfunction "2_P$2") (pintype "passive"))
    )
    (net (code "193") (name "Net-(R50-2)") (class "Default")
      (node (ref "D50") (pin "A") (pinfunction "A_A") (pintype "passive"))
      (node (ref "R50") (pin "P$2") (pinfunction "2_P$2") (pintype "passive"))
    )
    (net (code "194") (name "Net-(R51-2)") (class "Default")
      (node (ref "D51") (pin "A") (pinfunction "A_A") (pintype "passive"))
      (node (ref "R51") (pin "P$2") (pinfunction "2_P$2") (pintype "passive"))
    )
    (net (code "195") (name "Net-(R52-2)") (class "Default")
      (node (ref "D52") (pin "A") (pinfunction "A_A") (pintype "passive"))
      (node (ref "R52") (pin "P$2") (pinfunction "2_P$2") (pintype "passive"))
    )
    (net (code "196") (name "Net-(R53-2)") (class "Default")
      (node (ref "D53") (pin "A") (pinfunction "A_A") (pintype "passive"))
      (node (ref "R53") (pin "P$2") (pinfunction "2_P$2") (pintype "passive"))
    )
    (net (code "197") (name "Net-(R54-2)") (class "Default")
      (node (ref "D54") (pin "A") (pinfunction "A_A") (pintype "passive"))
      (node (ref "R54") (pin "P$2") (pinfunction "2_P$2") (pintype "passive"))
    )
    (net (code "198") (name "Net-(R55-2)") (class "Default")
      (node (ref "D55") (pin "A") (pinfunction "A_A") (pintype "passive"))
      (node (ref "R55") (pin "P$2") (pinfunction "2_P$2") (pintype "passive"))
    )
    (net (code "199") (name "Net-(R56-2)") (class "Default")
      (node (ref "D56") (pin "A") (pinfunction "A_A") (pintype "passive"))
      (node (ref "R56") (pin "P$2") (pinfunction "2_P$2") (pintype "passive"))
    )
    (net (code "200") (name "Net-(R57-2)") (class "Default")
      (node (ref "D57") (pin "A") (pinfunction "A_A") (pintype "passive"))
      (node (ref "R57") (pin "P$2") (pinfunction "2_P$2") (pintype "passive"))
    )
    (net (code "201") (name "Net-(R58-2)") (class "Default")
      (node (ref "D58") (pin "A") (pinfunction "A_A") (pintype "passive"))
      (node (ref "R58") (pin "P$2") (pinfunction "2_P$2") (pintype "passive"))
    )
    (net (code "202") (name "Net-(R59-2)") (class "Default")
      (node (ref "D59") (pin "A") (pinfunction "A_A") (pintype "passive"))
      (node (ref "R59") (pin "P$2") (pinfunction "2_P$2") (pintype "passive"))
    )
    (net (code "203") (name "Net-(R60-2)") (class "Default")
      (node (ref "D60") (pin "A") (pinfunction "A_A") (pintype "passive"))
      (node (ref "R60") (pin "P$2") (pinfunction "2_P$2") (pintype "passive"))
    )
    (net (code "204") (name "Net-(R61-2)") (class "Default")
      (node (ref "HD1") (pin "A") (pinfunction "A_A") (pintype "passive"))
      (node (ref "R61") (pin "P$2") (pinfunction "2_P$2") (pintype "passive"))
    )
    (net (code "205") (name "Net-(R62-2)") (class "Default")
      (node (ref "H1") (pin "A") (pinfunction "A_A") (pintype "passive"))
      (node (ref "R62") (pin "P$2") (pinfunction "2_P$2") (pintype "passive"))
    )
    (net (code "206") (name "Net-(R63-2)") (class "Default")
      (node (ref "HD2") (pin "A") (pinfunction "A_A") (pintype "passive"))
      (node (ref "R63") (pin "P$2") (pinfunction "2_P$2") (pintype "passive"))
    )
    (net (code "207") (name "Net-(R64-2)") (class "Default")
      (node (ref "H2") (pin "A") (pinfunction "A_A") (pintype "passive"))
      (node (ref "R64") (pin "P$2") (pinfunction "2_P$2") (pintype "passive"))
    )
    (net (code "208") (name "Net-(R65-2)") (class "Default")
      (node (ref "HD3") (pin "A") (pinfunction "A_A") (pintype "passive"))
      (node (ref "R65") (pin "P$2") (pinfunction "2_P$2") (pintype "passive"))
    )
    (net (code "209") (name "Net-(R66-2)") (class "Default")
      (node (ref "H3") (pin "A") (pinfunction "A_A") (pintype "passive"))
      (node (ref "R66") (pin "P$2") (pinfunction "2_P$2") (pintype "passive"))
    )
    (net (code "210") (name "Net-(R67-2)") (class "Default")
      (node (ref "HD4") (pin "A") (pinfunction "A_A") (pintype "passive"))
      (node (ref "R67") (pin "P$2") (pinfunction "2_P$2") (pintype "passive"))
    )
    (net (code "211") (name "Net-(R68-2)") (class "Default")
      (node (ref "H4") (pin "A") (pinfunction "A_A") (pintype "passive"))
      (node (ref "R68") (pin "P$2") (pinfunction "2_P$2") (pintype "passive"))
    )
    (net (code "212") (name "Net-(R69-2)") (class "Default")
      (node (ref "HD5") (pin "A") (pinfunction "A_A") (pintype "passive"))
      (node (ref "R69") (pin "P$2") (pinfunction "2_P$2") (pintype "passive"))
    )
    (net (code "213") (name "Net-(R70-2)") (class "Default")
      (node (ref "H5") (pin "A") (pinfunction "A_A") (pintype "passive"))
      (node (ref "R70") (pin "P$2") (pinfunction "2_P$2") (pintype "passive"))
    )
    (net (code "214") (name "Net-(R71-2)") (class "Default")
      (node (ref "HD6") (pin "A") (pinfunction "A_A") (pintype "passive"))
      (node (ref "R71") (pin "P$2") (pinfunction "2_P$2") (pintype "passive"))
    )
    (net (code "215") (name "Net-(R72-2)") (class "Default")
      (node (ref "H6") (pin "A") (pinfunction "A_A") (pintype "passive"))
      (node (ref "R72") (pin "P$2") (pinfunction "2_P$2") (pintype "passive"))
    )
    (net (code "216") (name "Net-(R73-2)") (class "Default")
      (node (ref "HD7") (pin "A") (pinfunction "A_A") (pintype "passive"))
      (node (ref "R73") (pin "P$2") (pinfunction "2_P$2") (pintype "passive"))
    )
    (net (code "217") (name "Net-(R74-2)") (class "Default")
      (node (ref "H7") (pin "A") (pinfunction "A_A") (pintype "passive"))
      (node (ref "R74") (pin "P$2") (pinfunction "2_P$2") (pintype "passive"))
    )
    (net (code "218") (name "Net-(R75-2)") (class "Default")
      (node (ref "HD8") (pin "A") (pinfunction "A_A") (pintype "passive"))
      (node (ref "R75") (pin "P$2") (pinfunction "2_P$2") (pintype "passive"))
    )
    (net (code "219") (name "Net-(R76-2)") (class "Default")
      (node (ref "H8") (pin "A") (pinfunction "A_A") (pintype "passive"))
      (node (ref "R76") (pin "P$2") (pinfunction "2_P$2") (pintype "passive"))
    )
    (net (code "220") (name "Net-(R77-2)") (class "Default")
      (node (ref "HD9") (pin "A") (pinfunction "A_A") (pintype "passive"))
      (node (ref "R77") (pin "P$2") (pinfunction "2_P$2") (pintype "passive"))
    )
    (net (code "221") (name "Net-(R78-2)") (class "Default")
      (node (ref "H9") (pin "A") (pinfunction "A_A") (pintype "passive"))
      (node (ref "R78") (pin "P$2") (pinfunction "2_P$2") (pintype "passive"))
    )
    (net (code "222") (name "Net-(R79-2)") (class "Default")
      (node (ref "HD10") (pin "A") (pinfunction "A_A") (pintype "passive"))
      (node (ref "R79") (pin "P$2") (pinfunction "2_P$2") (pintype "passive"))
    )
    (net (code "223") (name "Net-(R80-2)") (class "Default")
      (node (ref "H10") (pin "A") (pinfunction "A_A") (pintype "passive"))
      (node (ref "R80") (pin "P$2") (pinfunction "2_P$2") (pintype "passive"))
    )
    (net (code "224") (name "Net-(R81-2)") (class "Default")
      (node (ref "HD11") (pin "A") (pinfunction "A_A") (pintype "passive"))
      (node (ref "R81") (pin "P$2") (pinfunction "2_P$2") (pintype "passive"))
    )
    (net (code "225") (name "Net-(R82-2)") (class "Default")
      (node (ref "H11") (pin "A") (pinfunction "A_A") (pintype "passive"))
      (node (ref "R82") (pin "P$2") (pinfunction "2_P$2") (pintype "passive"))
    )
    (net (code "226") (name "Net-(R83-2)") (class "Default")
      (node (ref "HD12") (pin "A") (pinfunction "A_A") (pintype "passive"))
      (node (ref "R83") (pin "P$2") (pinfunction "2_P$2") (pintype "passive"))
    )
    (net (code "227") (name "Net-(R84-2)") (class "Default")
      (node (ref "H12") (pin "A") (pinfunction "A_A") (pintype "passive"))
      (node (ref "R84") (pin "P$2") (pinfunction "2_P$2") (pintype "passive"))
    )
    (net (code "228") (name "Net-(R127-1)") (class "Default")
      (node (ref "J3") (pin "4") (pinfunction "4_4") (pintype "passive"))
      (node (ref "R127") (pin "P$1") (pinfunction "1_P$1") (pintype "passive"))
    )
    (net (code "229") (name "Net-(R128-1)") (class "Default")
      (node (ref "J3") (pin "2") (pinfunction "2_2") (pintype "passive"))
      (node (ref "R128") (pin "P$1") (pinfunction "1_P$1") (pintype "passive"))
    )
    (net (code "230") (name "Net-(R129-1)") (class "Default")
      (node (ref "J3") (pin "3") (pinfunction "3_3") (pintype "passive"))
      (node (ref "R129") (pin "P$1") (pinfunction "1_P$1") (pintype "passive"))
    )
    (net (code "231") (name "SUP") (class "Default")
      (node (ref "D1") (pin "K") (pinfunction "C_K") (pintype "passive"))
      (node (ref "D10") (pin "K") (pinfunction "C_K") (pintype "passive"))
      (node (ref "D11") (pin "K") (pinfunction "C_K") (pintype "passive"))
      (node (ref "D12") (pin "K") (pinfunction "C_K") (pintype "passive"))
      (node (ref "D13") (pin "K") (pinfunction "C_K") (pintype "passive"))
      (node (ref "D14") (pin "K") (pinfunction "C_K") (pintype "passive"))
      (node (ref "D15") (pin "K") (pinfunction "C_K") (pintype "passive"))
      (node (ref "D16") (pin "K") (pinfunction "C_K") (pintype "passive"))
      (node (ref "D17") (pin "K") (pinfunction "C_K") (pintype "passive"))
      (node (ref "D18") (pin "K") (pinfunction "C_K") (pintype "passive"))
      (node (ref "D19") (pin "K") (pinfunction "C_K") (pintype "passive"))
      (node (ref "D2") (pin "K") (pinfunction "C_K") (pintype "passive"))
      (node (ref "D20") (pin "K") (pinfunction "C_K") (pintype "passive"))
      (node (ref "D21") (pin "K") (pinfunction "C_K") (pintype "passive"))
      (node (ref "D22") (pin "K") (pinfunction "C_K") (pintype "passive"))
      (node (ref "D23") (pin "K") (pinfunction "C_K") (pintype "passive"))
      (node (ref "D24") (pin "K") (pinfunction "C_K") (pintype "passive"))
      (node (ref "D25") (pin "K") (pinfunction "C_K") (pintype "passive"))
      (node (ref "D26") (pin "K") (pinfunction "C_K") (pintype "passive"))
      (node (ref "D27") (pin "K") (pinfunction "C_K") (pintype "passive"))
      (node (ref "D28") (pin "K") (pinfunction "C_K") (pintype "passive"))
      (node (ref "D29") (pin "K") (pinfunction "C_K") (pintype "passive"))
      (node (ref "D3") (pin "K") (pinfunction "C_K") (pintype "passive"))
      (node (ref "D30") (pin "K") (pinfunction "C_K") (pintype "passive"))
      (node (ref "D31") (pin "K") (pinfunction "C_K") (pintype "passive"))
      (node (ref "D32") (pin "K") (pinfunction "C_K") (pintype "passive"))
      (node (ref "D33") (pin "K") (pinfunction "C_K") (pintype "passive"))
      (node (ref "D34") (pin "K") (pinfunction "C_K") (pintype "passive"))
      (node (ref "D35") (pin "K") (pinfunction "C_K") (pintype "passive"))
      (node (ref "D36") (pin "K") (pinfunction "C_K") (pintype "passive"))
      (node (ref "D37") (pin "K") (pinfunction "C_K") (pintype "passive"))
      (node (ref "D38") (pin "K") (pinfunction "C_K") (pintype "passive"))
      (node (ref "D39") (pin "K") (pinfunction "C_K") (pintype "passive"))
      (node (ref "D4") (pin "K") (pinfunction "C_K") (pintype "passive"))
      (node (ref "D40") (pin "K") (pinfunction "C_K") (pintype "passive"))
      (node (ref "D41") (pin "K") (pinfunction "C_K") (pintype "passive"))
      (node (ref "D42") (pin "K") (pinfunction "C_K") (pintype "passive"))
      (node (ref "D43") (pin "K") (pinfunction "C_K") (pintype "passive"))
      (node (ref "D44") (pin "K") (pinfunction "C_K") (pintype "passive"))
      (node (ref "D45") (pin "K") (pinfunction "C_K") (pintype "passive"))
      (node (ref "D46") (pin "K") (pinfunction "C_K") (pintype "passive"))
      (node (ref "D47") (pin "K") (pinfunction "C_K") (pintype "passive"))
      (node (ref "D48") (pin "K") (pinfunction "C_K") (pintype "passive"))
      (node (ref "D49") (pin "K") (pinfunction "C_K") (pintype "passive"))
      (node (ref "D5") (pin "K") (pinfunction "C_K") (pintype "passive"))
      (node (ref "D50") (pin "K") (pinfunction "C_K") (pintype "passive"))
      (node (ref "D51") (pin "K") (pinfunction "C_K") (pintype "passive"))
      (node (ref "D52") (pin "K") (pinfunction "C_K") (pintype "passive"))
      (node (ref "D53") (pin "K") (pinfunction "C_K") (pintype "passive"))
      (node (ref "D54") (pin "K") (pinfunction "C_K") (pintype "passive"))
      (node (ref "D55") (pin "K") (pinfunction "C_K") (pintype "passive"))
      (node (ref "D56") (pin "K") (pinfunction "C_K") (pintype "passive"))
      (node (ref "D57") (pin "K") (pinfunction "C_K") (pintype "passive"))
      (node (ref "D58") (pin "K") (pinfunction "C_K") (pintype "passive"))
      (node (ref "D59") (pin "K") (pinfunction "C_K") (pintype "passive"))
      (node (ref "D6") (pin "K") (pinfunction "C_K") (pintype "passive"))
      (node (ref "D60") (pin "K") (pinfunction "C_K") (pintype "passive"))
      (node (ref "D7") (pin "K") (pinfunction "C_K") (pintype "passive"))
      (node (ref "D8") (pin "K") (pinfunction "C_K") (pintype "passive"))
      (node (ref "D9") (pin "K") (pinfunction "C_K") (pintype "passive"))
      (node (ref "H1") (pin "K") (pinfunction "C_K") (pintype "passive"))
      (node (ref "H10") (pin "K") (pinfunction "C_K") (pintype "passive"))
      (node (ref "H11") (pin "K") (pinfunction "C_K") (pintype "passive"))
      (node (ref "H12") (pin "K") (pinfunction "C_K") (pintype "passive"))
      (node (ref "H2") (pin "K") (pinfunction "C_K") (pintype "passive"))
      (node (ref "H3") (pin "K") (pinfunction "C_K") (pintype "passive"))
      (node (ref "H4") (pin "K") (pinfunction "C_K") (pintype "passive"))
      (node (ref "H5") (pin "K") (pinfunction "C_K") (pintype "passive"))
      (node (ref "H6") (pin "K") (pinfunction "C_K") (pintype "passive"))
      (node (ref "H7") (pin "K") (pinfunction "C_K") (pintype "passive"))
      (node (ref "H8") (pin "K") (pinfunction "C_K") (pintype "passive"))
      (node (ref "H9") (pin "K") (pinfunction "C_K") (pintype "passive"))
      (node (ref "HD1") (pin "K") (pinfunction "C_K") (pintype "passive"))
      (node (ref "HD10") (pin "K") (pinfunction "C_K") (pintype "passive"))
      (node (ref "HD11") (pin "K") (pinfunction "C_K") (pintype "passive"))
      (node (ref "HD12") (pin "K") (pinfunction "C_K") (pintype "passive"))
      (node (ref "HD2") (pin "K") (pinfunction "C_K") (pintype "passive"))
      (node (ref "HD3") (pin "K") (pinfunction "C_K") (pintype "passive"))
      (node (ref "HD4") (pin "K") (pinfunction "C_K") (pintype "passive"))
      (node (ref "HD5") (pin "K") (pinfunction "C_K") (pintype "passive"))
      (node (ref "HD6") (pin "K") (pinfunction "C_K") (pintype "passive"))
      (node (ref "HD7") (pin "K") (pinfunction "C_K") (pintype "passive"))
      (node (ref "HD8") (pin "K") (pinfunction "C_K") (pintype "passive"))
      (node (ref "HD9") (pin "K") (pinfunction "C_K") (pintype "passive"))
      (node (ref "J2") (pin "GND@1") (pinfunction "GNDBREAK_GND@1") (pintype "bidirectional"))
      (node (ref "J2") (pin "GND@2") (pinfunction "GND_GND@2") (pintype "bidirectional"))
      (node (ref "J3") (pin "5") (pinfunction "5_5") (pintype "passive"))
      (node (ref "M1") (pin "J1.4") (pinfunction "GND.1_J1.4") (pintype "power_in"))
      (node (ref "M1") (pin "J2.2") (pinfunction "GND.2_J2.2") (pintype "power_in"))
      (node (ref "R139") (pin "P$1") (pinfunction "1_P$1") (pintype "passive"))
      (node (ref "R141") (pin "P$1") (pinfunction "1_P$1") (pintype "passive"))
      (node (ref "R143") (pin "P$1") (pinfunction "1_P$1") (pintype "passive"))
      (node (ref "R145") (pin "P$1") (pinfunction "1_P$1") (pintype "passive"))
      (node (ref "R147") (pin "P$1") (pinfunction "1_P$1") (pintype "passive"))
      (node (ref "R149") (pin "P$1") (pinfunction "1_P$1") (pintype "passive"))
      (node (ref "R151") (pin "P$1") (pinfunction "1_P$1") (pintype "passive"))
      (node (ref "R153") (pin "P$1") (pinfunction "1_P$1") (pintype "passive"))
      (node (ref "R155") (pin "P$1") (pinfunction "1_P$1") (pintype "passive"))
      (node (ref "R157") (pin "P$1") (pinfunction "1_P$1") (pintype "passive"))
      (node (ref "R159") (pin "P$1") (pinfunction "1_P$1") (pintype "passive"))
      (node (ref "U$1") (pin "J1.1") (pinfunction "GND.1_J1.1") (pintype "power_in"))
    )
    (net (code "232") (name "VCC") (class "Default")
      (node (ref "J2") (pin "PWR") (pinfunction "PWR_PWR") (pintype "bidirectional"))
      (node (ref "J3") (pin "1") (pinfunction "1_1") (pintype "passive"))
      (node (ref "M1") (pin "J2.4") (pinfunction "5V_J2.4") (pintype "power_in"))
      (node (ref "R138") (pin "P$1") (pinfunction "1_P$1") (pintype "passive"))
      (node (ref "R140") (pin "P$1") (pinfunction "1_P$1") (pintype "passive"))
      (node (ref "R142") (pin "P$1") (pinfunction "1_P$1") (pintype "passive"))
      (node (ref "R144") (pin "P$1") (pinfunction "1_P$1") (pintype "passive"))
      (node (ref "R146") (pin "P$1") (pinfunction "1_P$1") (pintype "passive"))
      (node (ref "R148") (pin "P$1") (pinfunction "1_P$1") (pintype "passive"))
      (node (ref "R150") (pin "P$1") (pinfunction "1_P$1") (pintype "passive"))
      (node (ref "R152") (pin "P$1") (pinfunction "1_P$1") (pintype "passive"))
      (node (ref "R154") (pin "P$1") (pinfunction "1_P$1") (pintype "passive"))
      (node (ref "R156") (pin "P$1") (pinfunction "1_P$1") (pintype "passive"))
      (node (ref "R158") (pin "P$1") (pinfunction "1_P$1") (pintype "passive"))
      (node (ref "U$1") (pin "J1.2") (pinfunction "VCC.1_J1.2") (pintype "power_in"))
    )
    (net (code "233") (name "unconnected-(ICH3A-QH*-Pad9)") (class "Default")
      (node (ref "ICH3") (pin "9") (pinfunction "QH*_9") (pintype "tri_state"))
    )
    (net (code "234") (name "unconnected-(ICL8A-QE-Pad4)") (class "Default")
      (node (ref "ICL8") (pin "4") (pinfunction "QE_4") (pintype "tri_state"))
    )
    (net (code "235") (name "unconnected-(ICL8A-QF-Pad5)") (class "Default")
      (node (ref "ICL8") (pin "5") (pinfunction "QF_5") (pintype "tri_state"))
    )
    (net (code "236") (name "unconnected-(ICL8A-QG-Pad6)") (class "Default")
      (node (ref "ICL8") (pin "6") (pinfunction "QG_6") (pintype "tri_state"))
    )
    (net (code "237") (name "unconnected-(ICL8A-QH*-Pad9)") (class "Default")
      (node (ref "ICL8") (pin "9") (pinfunction "QH*_9") (pintype "tri_state"))
    )
    (net (code "238") (name "unconnected-(ICL8A-QH-Pad7)") (class "Default")
      (node (ref "ICL8") (pin "7") (pinfunction "QH_7") (pintype "tri_state"))
    )
    (net (code "239") (name "unconnected-(M1-A6-PadJ2.6)") (class "Default")
      (node (ref "M1") (pin "J2.6") (pinfunction "A6_J2.6") (pintype "bidirectional"))
    )
    (net (code "240") (name "unconnected-(M1-A7-PadJ2.5)") (class "Default")
      (node (ref "M1") (pin "J2.5") (pinfunction "A7_J2.5") (pintype "bidirectional"))
    )
    (net (code "241") (name "unconnected-(M1-AREF-PadJ2.13)") (class "Default")
      (node (ref "M1") (pin "J2.13") (pinfunction "AREF_J2.13") (pintype "bidirectional"))
    )
    (net (code "242") (name "unconnected-(M1-D0{slash}RX-PadJ1.2)") (class "Default")
      (node (ref "M1") (pin "J1.2") (pinfunction "D0/RX_J1.2") (pintype "bidirectional"))
    )
    (net (code "243") (name "unconnected-(M1-D1{slash}TX-PadJ1.1)") (class "Default")
      (node (ref "M1") (pin "J1.1") (pinfunction "D1/TX_J1.1") (pintype "bidirectional"))
    )
    (net (code "244") (name "unconnected-(M1-RST.1-PadJ1.3)") (class "Default")
      (node (ref "M1") (pin "J1.3") (pinfunction "RST.1_J1.3") (pintype "bidirectional"))
    )
    (net (code "245") (name "unconnected-(M1-RST.2-PadJ2.3)") (class "Default")
      (node (ref "M1") (pin "J2.3") (pinfunction "RST.2_J2.3") (pintype "bidirectional"))
    )
    (net (code "246") (name "unconnected-(U$1-BAT-PadJ2.1)") (class "Default")
      (node (ref "U$1") (pin "J2.1") (pinfunction "BAT_J2.1") (pintype "bidirectional"))
    )
    (net (code "247") (name "unconnected-(U$1-DS.1-PadJ1.5)") (class "Default")
      (node (ref "U$1") (pin "J1.5") (pinfunction "DS.1_J1.5") (pintype "bidirectional"))
    )
    (net (code "248") (name "unconnected-(U$1-DS.2-PadJ2.6)") (class "Default")
      (node (ref "U$1") (pin "J2.6") (pinfunction "DS.2_J2.6") (pintype "bidirectional"))
    )
    (net (code "249") (name "unconnected-(U$1-SCL.2-PadJ2.5)") (class "Default")
      (node (ref "U$1") (pin "J2.5") (pinfunction "SCL.2_J2.5") (pintype "bidirectional"))
    )
    (net (code "250") (name "unconnected-(U$1-SDA.2-PadJ2.4)") (class "Default")
      (node (ref "U$1") (pin "J2.4") (pinfunction "SDA.2_J2.4") (pintype "bidirectional"))
    )
    (net (code "251") (name "unconnected-(U$1-SQ-PadJ2.7)") (class "Default")
      (node (ref "U$1") (pin "J2.7") (pinfunction "SQ_J2.7") (pintype "bidirectional"))
    )
  )
)
